# BSB-LAN-Full-SS.net
KiCad netlist of a schematic drawn in EAGLE
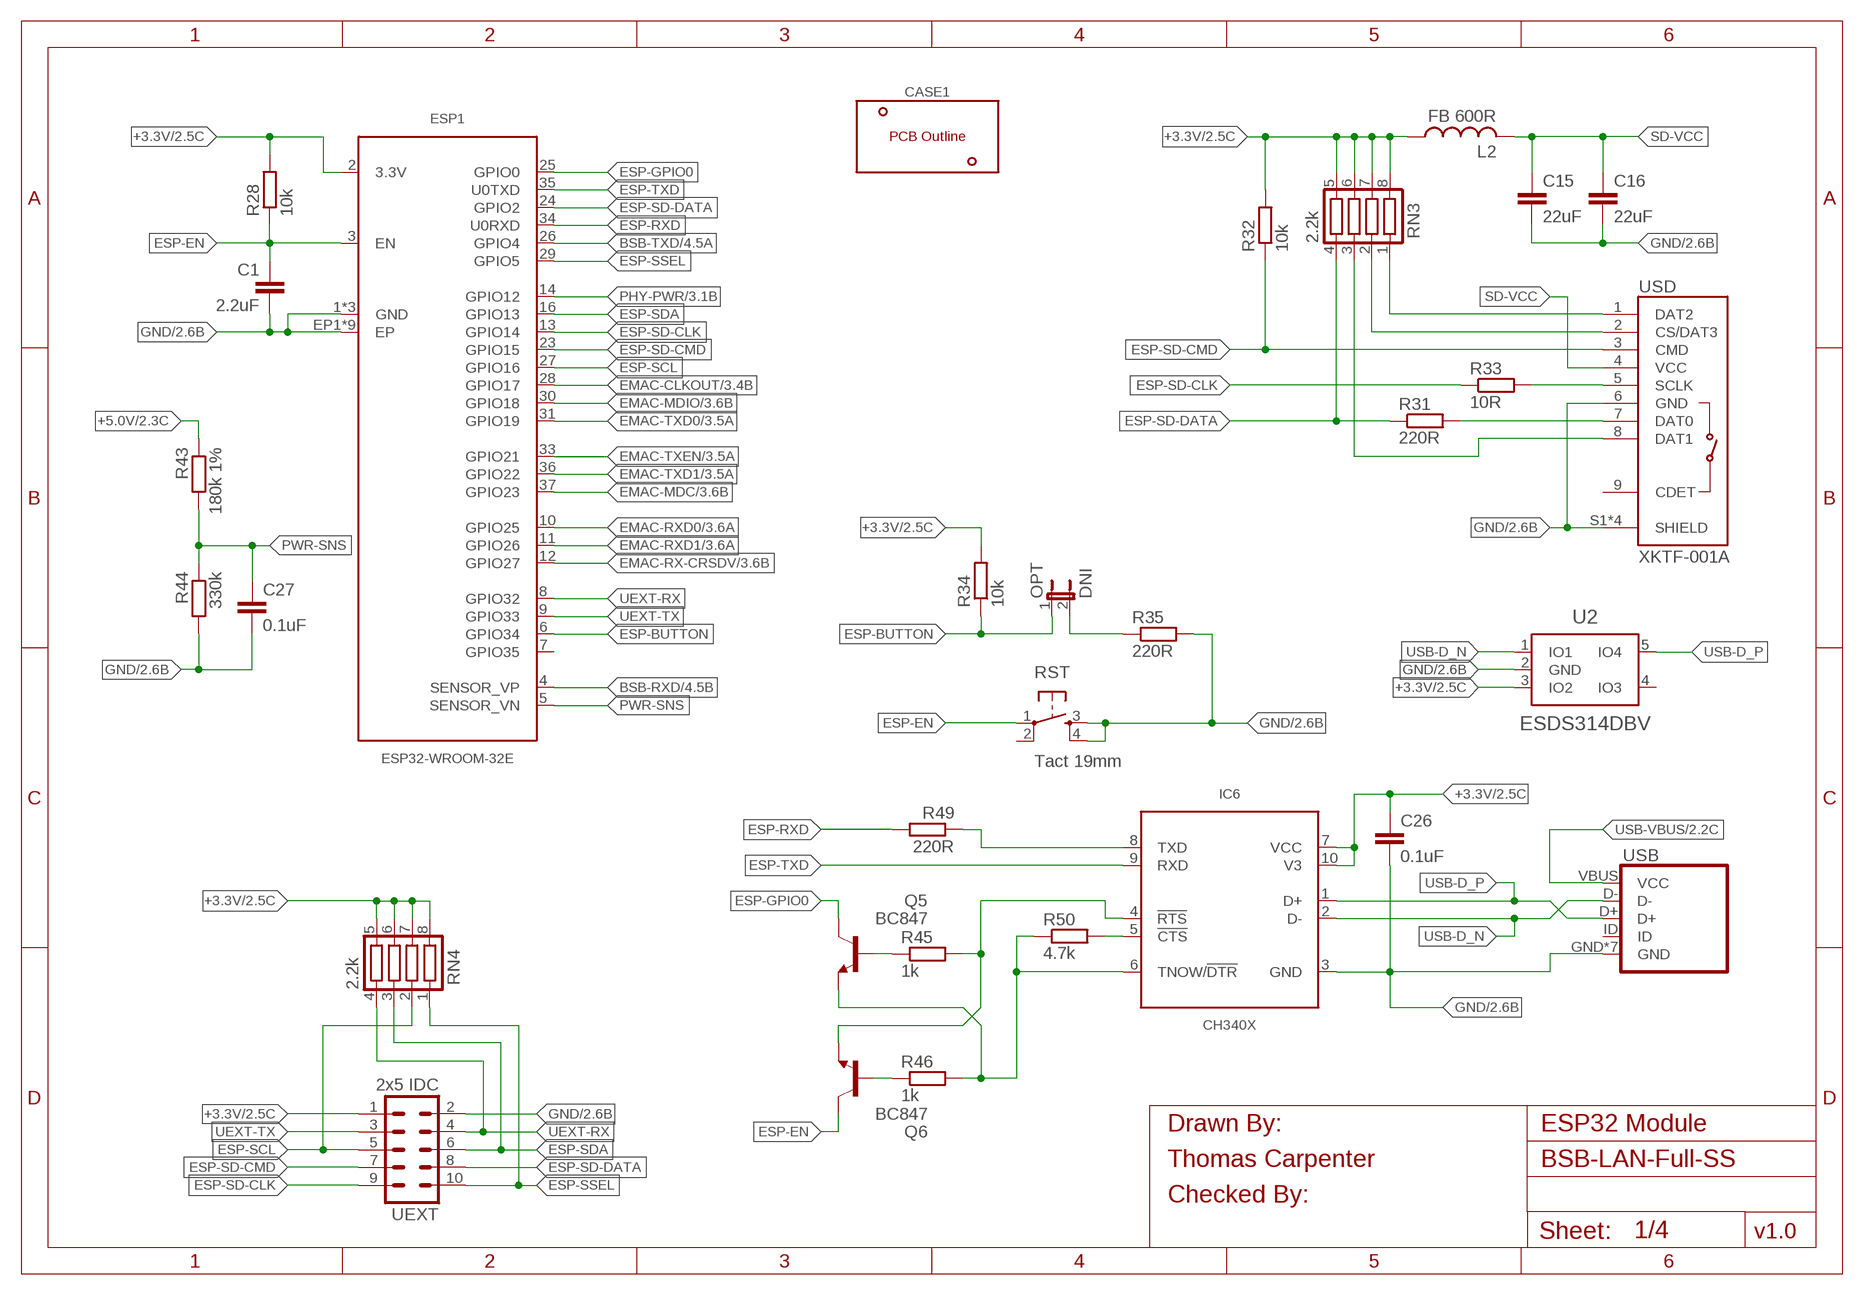
[diagram p0: schematic, sheet 1]
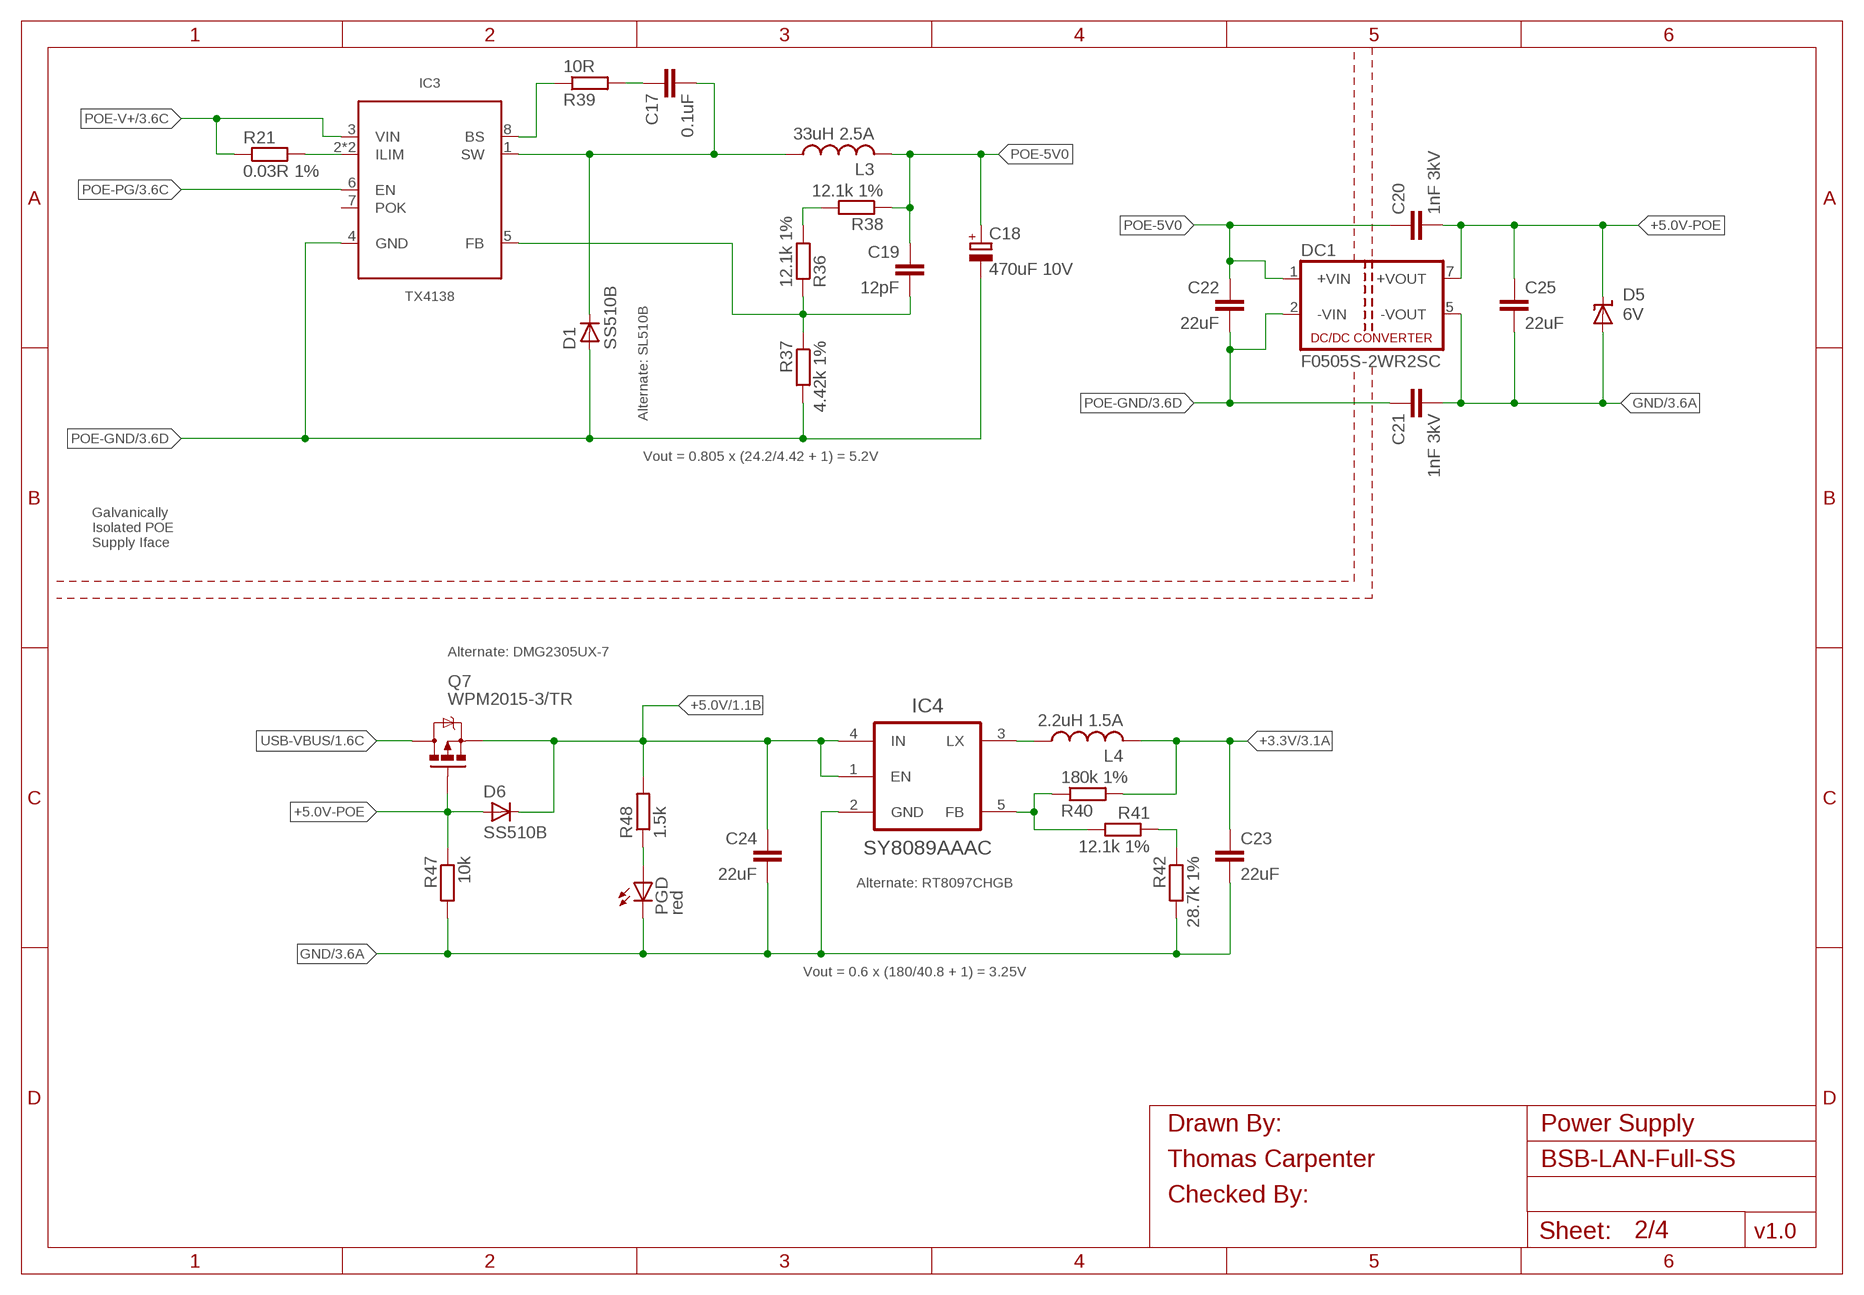
[diagram p1: schematic, sheet 2]
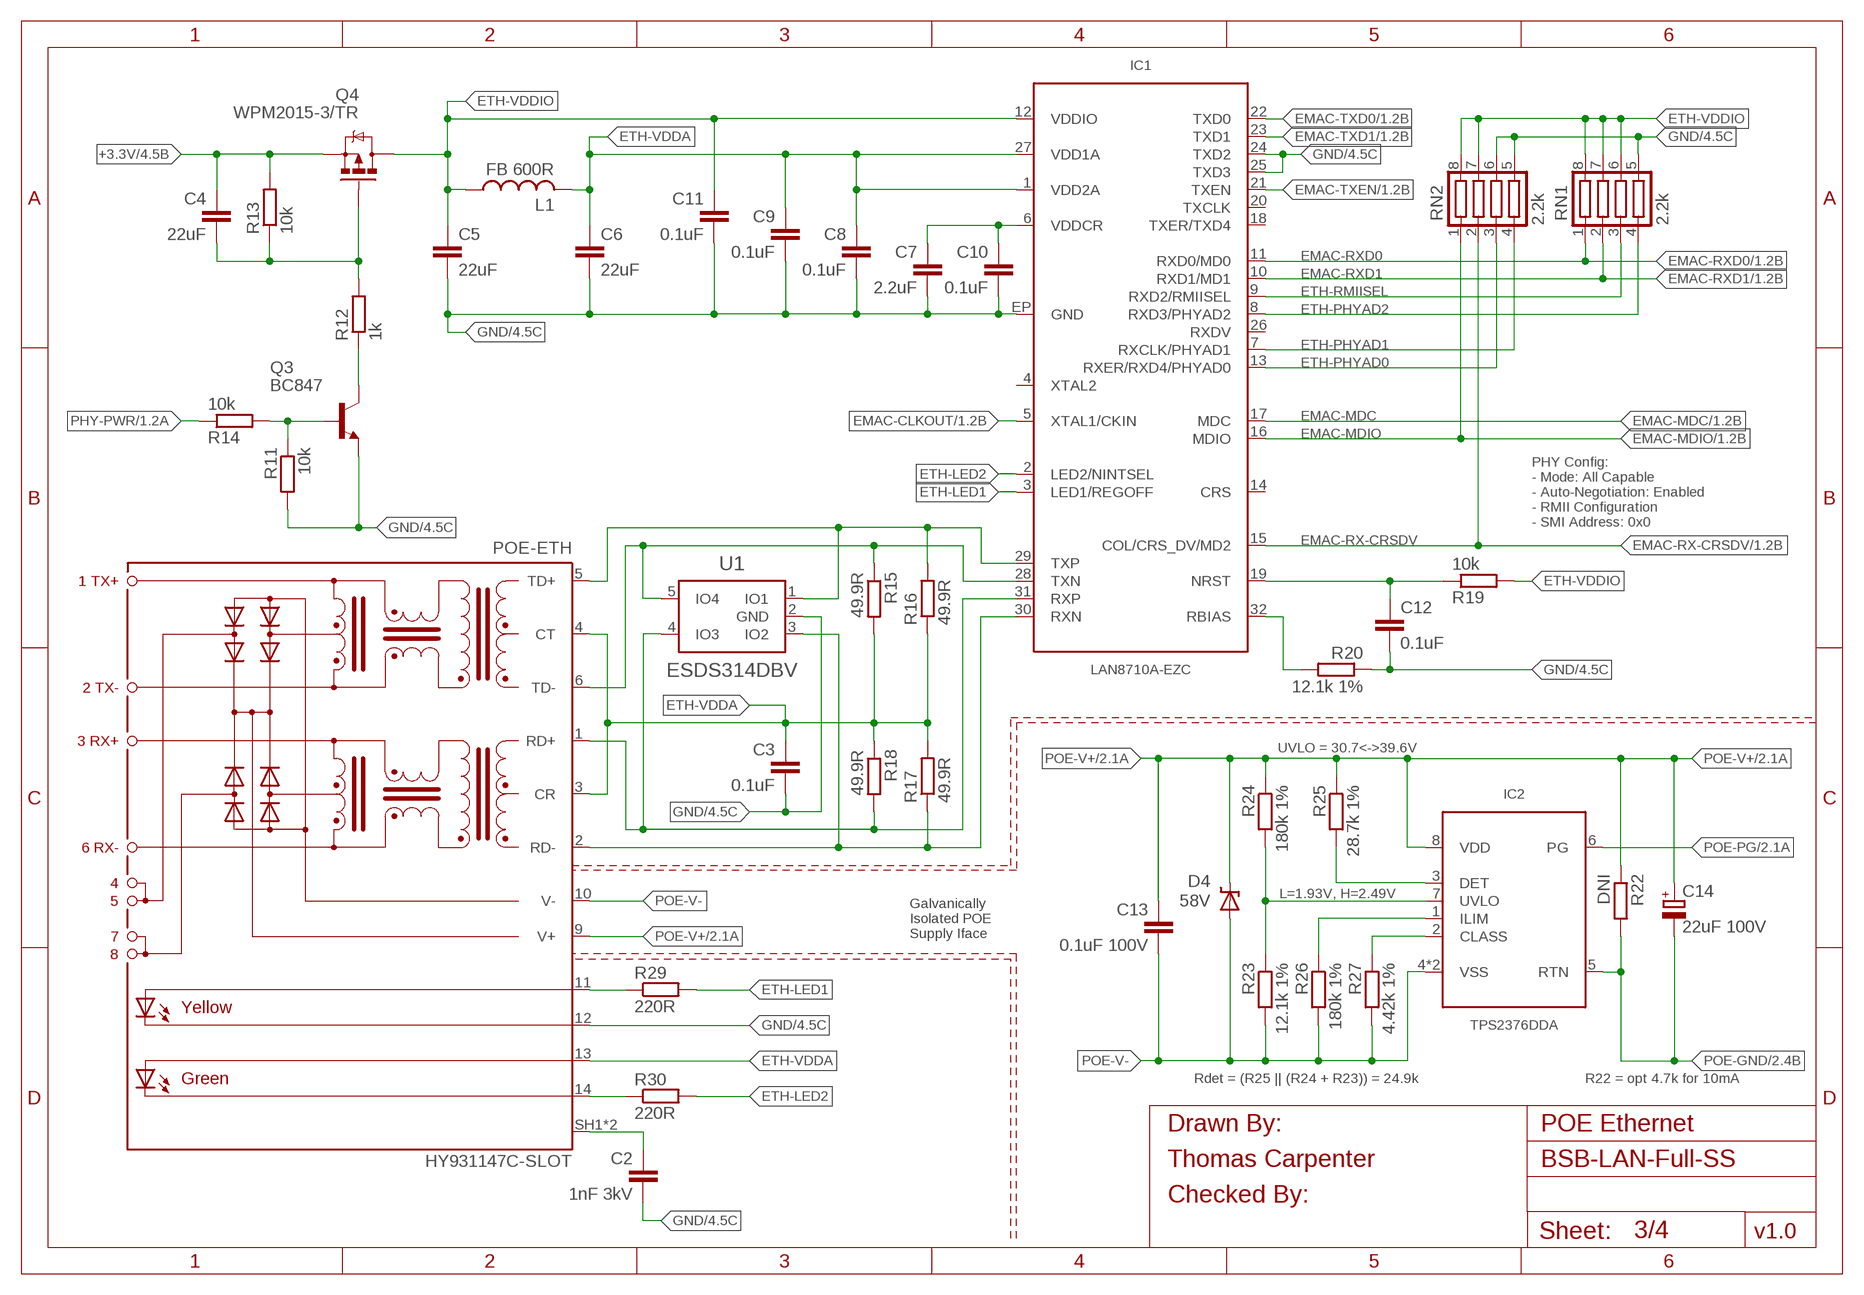
[diagram p2: schematic, sheet 3]
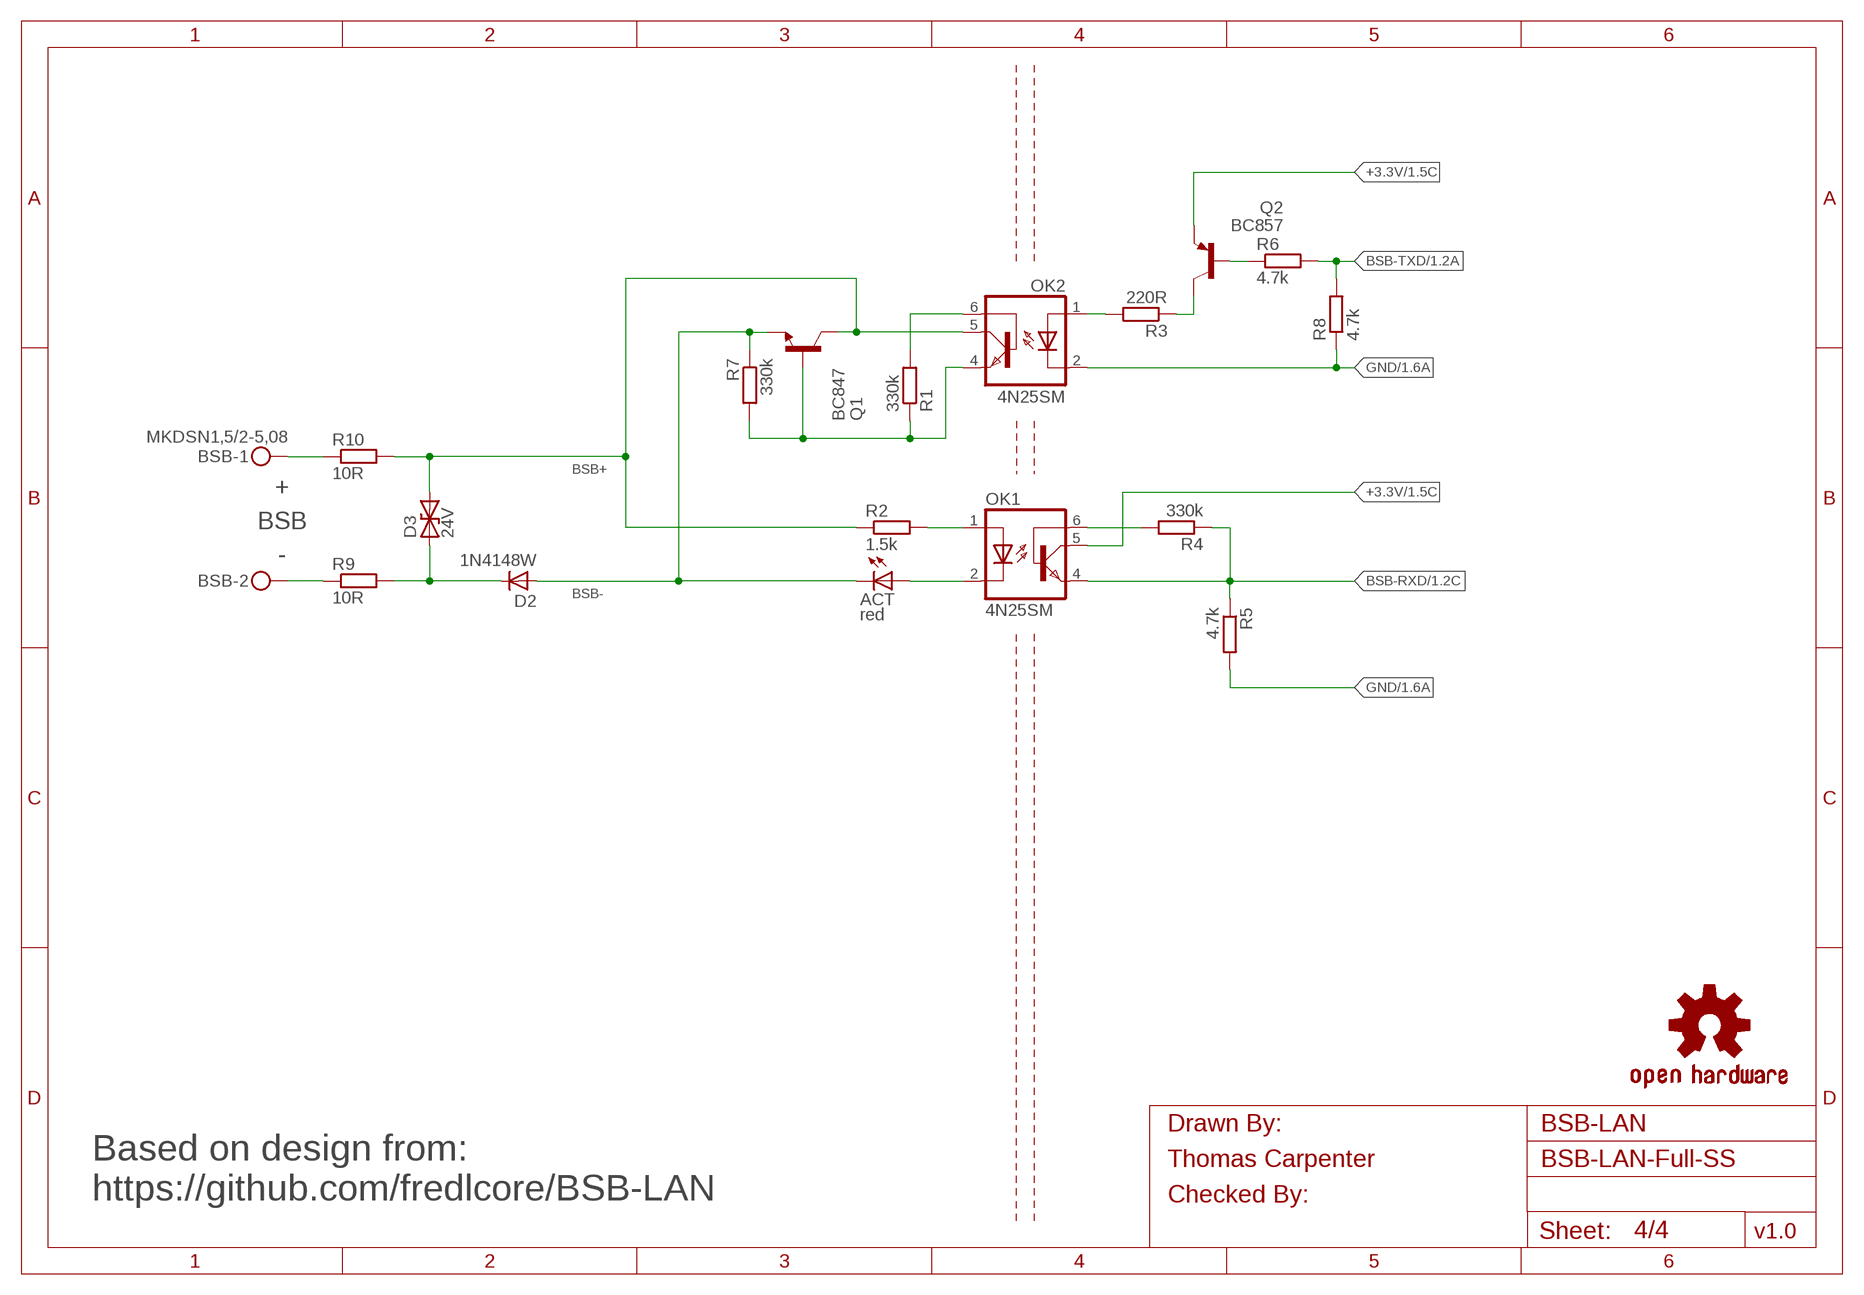
[diagram p3: schematic, sheet 4]

(export (version "E")
  (design (tool "Eeschema 10.0.6"))
  (components
    (comp (ref "C17")
      (value "0.1uF")
      (footprint "eagle-import:C0603L")
      (fields (field (name "LCSC_PART") "C113803"))
      (libsource (lib "eagle-import") (part "C-EUC0603L"))
    )
    (comp (ref "C18")
      (value "470uF 10V")
      (footprint "eagle-import:SMC_D")
      (fields (field (name "LCSC_PART") "C4944894"))
      (libsource (lib "eagle-import") (part "CPOL-EUSMCD"))
    )
    (comp (ref "C19")
      (value "12pF")
      (footprint "eagle-import:C0402")
      (fields (field (name "LCSC_PART") "C1547"))
      (libsource (lib "eagle-import") (part "C-EUC0402"))
    )
    (comp (ref "C20")
      (value "1nF 3kV")
      (footprint "eagle-import:C1808")
      (fields (field (name "LCSC_PART") "C577300"))
      (libsource (lib "eagle-import") (part "C-EUC1808"))
    )
    (comp (ref "C21")
      (value "1nF 3kV")
      (footprint "eagle-import:C1808")
      (fields (field (name "LCSC_PART") "C577300"))
      (libsource (lib "eagle-import") (part "C-EUC1808"))
    )
    (comp (ref "C22")
      (value "22uF")
      (footprint "eagle-import:C0805")
      (fields (field (name "LCSC_PART") "C45783"))
      (libsource (lib "eagle-import") (part "C-EUC0805"))
    )
    (comp (ref "C23")
      (value "22uF")
      (footprint "eagle-import:C0805")
      (fields (field (name "LCSC_PART") "C45783"))
      (libsource (lib "eagle-import") (part "C-EUC0805"))
    )
    (comp (ref "C24")
      (value "22uF")
      (footprint "eagle-import:C0805")
      (fields (field (name "LCSC_PART") "C45783"))
      (libsource (lib "eagle-import") (part "C-EUC0805"))
    )
    (comp (ref "C25")
      (value "22uF")
      (footprint "eagle-import:C0805")
      (fields (field (name "LCSC_PART") "C45783"))
      (libsource (lib "eagle-import") (part "C-EUC0805"))
    )
    (comp (ref "D1")
      (value "SS510B")
      (footprint "eagle-import:SMB")
      (fields (field (name "LCSC_PART") "C65011"))
      (libsource (lib "eagle-import") (part "DIODE-SMB"))
    )
    (comp (ref "D5")
      (value "6V")
      (footprint "eagle-import:SMA")
      (fields (field (name "LCSC_PART") "C223993"))
      (libsource (lib "eagle-import") (part "TVS-UNISMA"))
    )
    (comp (ref "D6")
      (value "SS510B")
      (footprint "eagle-import:SMB")
      (fields (field (name "LCSC_PART") "C65011"))
      (libsource (lib "eagle-import") (part "DIODE-SMB"))
    )
    (comp (ref "DC1")
      (value "F0505S-2WR2SC")
      (footprint "eagle-import:SIP7-N")
      (fields (field (name "LCSC_PART") "C909777"))
      (libsource (lib "eagle-import") (part "FS-2WR2SC0505"))
    )
    (comp (ref "IC3")
      (value "TX4138")
      (footprint "eagle-import:SOIC8-EP")
      (fields (field (name "LCSC_PART") "C329267"))
      (libsource (lib "eagle-import") (part "TX4138"))
    )
    (comp (ref "IC4")
      (value "SY8089AAAC")
      (footprint "eagle-import:DBV0005A-SOT23")
      (fields (field (name "LCSC_PART") "C78988"))
      (libsource (lib "eagle-import") (part "SY8089?CAAA"))
    )
    (comp (ref "L3")
      (value "33uH 2.5A")
      (footprint "eagle-import:L6560P")
      (fields (field (name "LCSC_PART") "C2839927"))
      (libsource (lib "eagle-import") (part "L-USL6560P"))
    )
    (comp (ref "L4")
      (value "2.2uH 1.5A")
      (footprint "eagle-import:L4040P")
      (fields (field (name "LCSC_PART") "C135262"))
      (libsource (lib "eagle-import") (part "L-USL4040P"))
    )
    (comp (ref "PGD")
      (value "red")
      (footprint "eagle-import:CHIP-LED0603")
      (fields (field (name "LCSC_PART") "C2286"))
      (libsource (lib "eagle-import") (part "LEDCHIPLED_0603"))
    )
    (comp (ref "Q7")
      (value "WPM2015-3/TR")
      (footprint "eagle-import:SOT23")
      (fields (field (name "LCSC_PART") "C7472861"))
      (libsource (lib "eagle-import") (part "WPM2015-3/TR"))
    )
    (comp (ref "R21")
      (value "0.03R 1%")
      (footprint "eagle-import:R1206")
      (fields (field (name "LCSC_PART") "C163046"))
      (libsource (lib "eagle-import") (part "R-EU_R1206"))
    )
    (comp (ref "R36")
      (value "12.1k 1%")
      (footprint "eagle-import:R0402")
      (fields (field (name "LCSC_PART") "C25852"))
      (libsource (lib "eagle-import") (part "R-EU_R0402"))
    )
    (comp (ref "R37")
      (value "4.42k 1%")
      (footprint "eagle-import:R0402")
      (fields (field (name "LCSC_PART") "C52269"))
      (libsource (lib "eagle-import") (part "R-EU_R0402"))
    )
    (comp (ref "R38")
      (value "12.1k 1%")
      (footprint "eagle-import:R0402")
      (fields (field (name "LCSC_PART") "C25852"))
      (libsource (lib "eagle-import") (part "R-EU_R0402"))
    )
    (comp (ref "R39")
      (value "10R")
      (footprint "eagle-import:R0603L")
      (fields (field (name "LCSC_PART") "C22859"))
      (libsource (lib "eagle-import") (part "R-EU_R0603L"))
    )
    (comp (ref "R40")
      (value "180k 1%")
      (footprint "eagle-import:R0402")
      (fields (field (name "LCSC_PART") "C25760"))
      (libsource (lib "eagle-import") (part "R-EU_R0402"))
    )
    (comp (ref "R41")
      (value "12.1k 1%")
      (footprint "eagle-import:R0402")
      (fields (field (name "LCSC_PART") "C25852"))
      (libsource (lib "eagle-import") (part "R-EU_R0402"))
    )
    (comp (ref "R42")
      (value "28.7k 1%")
      (footprint "eagle-import:R0402")
      (fields (field (name "LCSC_PART") "C26972"))
      (libsource (lib "eagle-import") (part "R-EU_R0402"))
    )
    (comp (ref "R47")
      (value "10k")
      (footprint "eagle-import:R0402")
      (fields (field (name "LCSC_PART") "C25744"))
      (libsource (lib "eagle-import") (part "R-EU_R0402"))
    )
    (comp (ref "R48")
      (value "1.5k")
      (footprint "eagle-import:R0603")
      (fields (field (name "LCSC_PART") "C22843"))
      (libsource (lib "eagle-import") (part "R-EU_R0603"))
    )
    (comp (ref "C2")
      (value "1nF 3kV")
      (footprint "eagle-import:C1808")
      (fields (field (name "LCSC_PART") "C577300"))
      (libsource (lib "eagle-import") (part "C-EUC1808"))
    )
    (comp (ref "C3")
      (value "0.1uF")
      (footprint "eagle-import:C0402")
      (fields (field (name "LCSC_PART") "C1525"))
      (libsource (lib "eagle-import") (part "C-EUC0402"))
    )
    (comp (ref "C4")
      (value "22uF")
      (footprint "eagle-import:C0805L")
      (fields (field (name "LCSC_PART") "C45783"))
      (libsource (lib "eagle-import") (part "C-EUC0805L"))
    )
    (comp (ref "C5")
      (value "22uF")
      (footprint "eagle-import:C0805L")
      (fields (field (name "LCSC_PART") "C45783"))
      (libsource (lib "eagle-import") (part "C-EUC0805L"))
    )
    (comp (ref "C6")
      (value "22uF")
      (footprint "eagle-import:C0805L")
      (fields (field (name "LCSC_PART") "C45783"))
      (libsource (lib "eagle-import") (part "C-EUC0805L"))
    )
    (comp (ref "C7")
      (value "2.2uF")
      (footprint "eagle-import:C0603")
      (fields (field (name "LCSC_PART") "C23630"))
      (libsource (lib "eagle-import") (part "C-EUC0603"))
    )
    (comp (ref "C8")
      (value "0.1uF")
      (footprint "eagle-import:C0402")
      (fields (field (name "LCSC_PART") "C1525"))
      (libsource (lib "eagle-import") (part "C-EUC0402"))
    )
    (comp (ref "C9")
      (value "0.1uF")
      (footprint "eagle-import:C0402")
      (fields (field (name "LCSC_PART") "C1525"))
      (libsource (lib "eagle-import") (part "C-EUC0402"))
    )
    (comp (ref "C10")
      (value "0.1uF")
      (footprint "eagle-import:C0402")
      (fields (field (name "LCSC_PART") "C1525"))
      (libsource (lib "eagle-import") (part "C-EUC0402"))
    )
    (comp (ref "C11")
      (value "0.1uF")
      (footprint "eagle-import:C0402")
      (fields (field (name "LCSC_PART") "C1525"))
      (libsource (lib "eagle-import") (part "C-EUC0402"))
    )
    (comp (ref "C12")
      (value "0.1uF")
      (footprint "eagle-import:C0402")
      (fields (field (name "LCSC_PART") "C1525"))
      (libsource (lib "eagle-import") (part "C-EUC0402"))
    )
    (comp (ref "C13")
      (value "0.1uF 100V")
      (footprint "eagle-import:C0603")
      (fields (field (name "LCSC_PART") "C113803"))
      (libsource (lib "eagle-import") (part "C-EUC0603"))
    )
    (comp (ref "C14")
      (value "22uF 100V")
      (footprint "eagle-import:PANASONIC_D")
      (fields (field (name "LCSC_PART") "C487431"))
      (libsource (lib "eagle-import") (part "CPOL-EUD"))
    )
    (comp (ref "D4")
      (value "58V")
      (footprint "eagle-import:SMA")
      (fields (field (name "LCSC_PART") "C151246"))
      (libsource (lib "eagle-import") (part "TVS-UNISMA"))
    )
    (comp (ref "IC1")
      (value "LAN8710A-EZC")
      (footprint "eagle-import:QFN-5X5-32")
      (fields (field (name "LCSC_PART") "C46185"))
      (libsource (lib "eagle-import") (part "LAN8710A-EZC"))
    )
    (comp (ref "IC2")
      (value "TPS2376DDA")
      (footprint "eagle-import:SOIC8-EP")
      (fields (field (name "LCSC_PART") "C544899"))
      (libsource (lib "eagle-import") (part "TPS237DDA6"))
    )
    (comp (ref "L1")
      (value "FB 600R")
      (footprint "eagle-import:L2010")
      (fields (field (name "LCSC_PART") "C1017"))
      (libsource (lib "eagle-import") (part "L-USL0805"))
    )
    (comp (ref "POE-ETH")
      (value "HY931147C-SLOT")
      (footprint "eagle-import:HY931147C-SLOT")
      (fields (field (name "LCSC_PART") "C91754"))
      (libsource (lib "eagle-import") (part "HY931147C-SLOT"))
    )
    (comp (ref "Q3")
      (value "BC847")
      (footprint "eagle-import:SOT23")
      (fields (field (name "LCSC_PART") "C130417"))
      (libsource (lib "eagle-import") (part "BC847"))
    )
    (comp (ref "Q4")
      (value "WPM2015-3/TR")
      (footprint "eagle-import:SOT23")
      (fields (field (name "LCSC_PART") "C7472861"))
      (libsource (lib "eagle-import") (part "WPM2015-3/TR"))
    )
    (comp (ref "R11")
      (value "10k")
      (footprint "eagle-import:R0402")
      (fields (field (name "LCSC_PART") "C25744"))
      (libsource (lib "eagle-import") (part "R-EU_R0402"))
    )
    (comp (ref "R12")
      (value "1k")
      (footprint "eagle-import:R0402")
      (fields (field (name "LCSC_PART") "C11702"))
      (libsource (lib "eagle-import") (part "R-EU_R0402"))
    )
    (comp (ref "R13")
      (value "10k")
      (footprint "eagle-import:R0402")
      (fields (field (name "LCSC_PART") "C25744"))
      (libsource (lib "eagle-import") (part "R-EU_R0402"))
    )
    (comp (ref "R14")
      (value "10k")
      (footprint "eagle-import:R0402")
      (fields (field (name "LCSC_PART") "C25744"))
      (libsource (lib "eagle-import") (part "R-EU_R0402"))
    )
    (comp (ref "R15")
      (value "49.9R")
      (footprint "eagle-import:R0402L")
      (fields (field (name "LCSC_PART") "C25120"))
      (libsource (lib "eagle-import") (part "R-EU_R0402L"))
    )
    (comp (ref "R16")
      (value "49.9R")
      (footprint "eagle-import:R0402L")
      (fields (field (name "LCSC_PART") "C25120"))
      (libsource (lib "eagle-import") (part "R-EU_R0402L"))
    )
    (comp (ref "R17")
      (value "49.9R")
      (footprint "eagle-import:R0402L")
      (fields (field (name "LCSC_PART") "C25120"))
      (libsource (lib "eagle-import") (part "R-EU_R0402L"))
    )
    (comp (ref "R18")
      (value "49.9R")
      (footprint "eagle-import:R0402L")
      (fields (field (name "LCSC_PART") "C25120"))
      (libsource (lib "eagle-import") (part "R-EU_R0402L"))
    )
    (comp (ref "R19")
      (value "10k")
      (footprint "eagle-import:R0402")
      (fields (field (name "LCSC_PART") "C25744"))
      (libsource (lib "eagle-import") (part "R-EU_R0402"))
    )
    (comp (ref "R20")
      (value "12.1k 1%")
      (footprint "eagle-import:R0402")
      (fields (field (name "LCSC_PART") "C25852"))
      (libsource (lib "eagle-import") (part "R-EU_R0402"))
    )
    (comp (ref "R22")
      (value "DNI")
      (footprint "eagle-import:R1206")
      (libsource (lib "eagle-import") (part "R-EU_R1206"))
    )
    (comp (ref "R23")
      (value "12.1k 1%")
      (footprint "eagle-import:R0402")
      (fields (field (name "LCSC_PART") "C25852"))
      (libsource (lib "eagle-import") (part "R-EU_R0402"))
    )
    (comp (ref "R24")
      (value "180k 1%")
      (footprint "eagle-import:R0402")
      (fields (field (name "LCSC_PART") "C25760"))
      (libsource (lib "eagle-import") (part "R-EU_R0402"))
    )
    (comp (ref "R25")
      (value "28.7k 1%")
      (footprint "eagle-import:R0402")
      (fields (field (name "LCSC_PART") "C26972"))
      (libsource (lib "eagle-import") (part "R-EU_R0402"))
    )
    (comp (ref "R26")
      (value "180k 1%")
      (footprint "eagle-import:R0402")
      (fields (field (name "LCSC_PART") "C25760"))
      (libsource (lib "eagle-import") (part "R-EU_R0402"))
    )
    (comp (ref "R27")
      (value "4.42k 1%")
      (footprint "eagle-import:R0402")
      (fields (field (name "LCSC_PART") "C52269"))
      (libsource (lib "eagle-import") (part "R-EU_R0402"))
    )
    (comp (ref "R29")
      (value "220R")
      (footprint "eagle-import:R0402")
      (fields (field (name "LCSC_PART") "C25091"))
      (libsource (lib "eagle-import") (part "R-EU_R0402"))
    )
    (comp (ref "R30")
      (value "220R")
      (footprint "eagle-import:R0402")
      (fields (field (name "LCSC_PART") "C25091"))
      (libsource (lib "eagle-import") (part "R-EU_R0402"))
    )
    (comp (ref "RN1")
      (value "2.2k")
      (footprint "eagle-import:CTS742C083")
      (fields (field (name "LCSC_PART") "C414564"))
      (libsource (lib "eagle-import") (part "R-NET-04-R1206"))
    )
    (comp (ref "RN2")
      (value "2.2k")
      (footprint "eagle-import:CTS742C083")
      (fields (field (name "LCSC_PART") "C414564"))
      (libsource (lib "eagle-import") (part "R-NET-04-R1206"))
    )
    (comp (ref "U1")
      (value "ESDS314DBV")
      (footprint "eagle-import:DBV0005A-SOT23")
      (fields (field (name "LCSC_PART") "C1847859"))
      (libsource (lib "eagle-import") (part "ESDS314DBV"))
    )
    (comp (ref "ACT")
      (value "red")
      (footprint "eagle-import:CHIP-LED0603")
      (fields (field (name "LCSC_PART") "C2286"))
      (libsource (lib "eagle-import") (part "LEDCHIPLED_0603"))
    )
    (comp (ref "BSB")
      (value "MKDSN1,5/2-5,08")
      (footprint "eagle-import:MKDSN1_5-2-5_08")
      (fields (field (name "LCSC_PART") "C5183989"))
      (libsource (lib "eagle-import") (part "MKDSN1,5/2-5,08"))
    )
    (comp (ref "D2")
      (value "1N4148W")
      (footprint "eagle-import:SOD123")
      (fields (field (name "LCSC_PART") "C81598"))
      (libsource (lib "eagle-import") (part "DIODE-SOD123"))
    )
    (comp (ref "D3")
      (value "24V")
      (footprint "eagle-import:SMBG")
      (fields (field (name "LCSC_PART") "C83268"))
      (libsource (lib "eagle-import") (part "TVS-BIDIRSMB"))
    )
    (comp (ref "OK1")
      (value "4N25SM")
      (footprint "eagle-import:DIL6-SMD")
      (fields (field (name "LCSC_PART") "C258246") (field (name "LCSC_PART_1") "C258246"))
      (libsource (lib "eagle-import") (part "4N?MS25"))
    )
    (comp (ref "OK2")
      (value "4N25SM")
      (footprint "eagle-import:DIL6-SMD")
      (fields (field (name "LCSC_PART") "C258246") (field (name "LCSC_PART_1") "C258246"))
      (libsource (lib "eagle-import") (part "4N?MS25"))
    )
    (comp (ref "Q1")
      (value "BC847")
      (footprint "eagle-import:SOT23")
      (fields (field (name "LCSC_PART") "C130417") (field (name "LCSC_PART_1") "C130417"))
      (libsource (lib "eagle-import") (part "BC847"))
    )
    (comp (ref "Q2")
      (value "BC857")
      (footprint "eagle-import:SOT23-BEC")
      (fields (field (name "LCSC_PART") "C426782") (field (name "LCSC_PART_1") "C426782"))
      (libsource (lib "eagle-import") (part "BC857"))
    )
    (comp (ref "R1")
      (value "330k")
      (footprint "eagle-import:R0603")
      (fields (field (name "LCSC_PART") "C23137"))
      (libsource (lib "eagle-import") (part "R-EU_R0603"))
    )
    (comp (ref "R2")
      (value "1.5k")
      (footprint "eagle-import:R0603")
      (fields (field (name "LCSC_PART") "C22843"))
      (libsource (lib "eagle-import") (part "R-EU_R0603"))
    )
    (comp (ref "R3")
      (value "220R")
      (footprint "eagle-import:R0402")
      (fields (field (name "LCSC_PART") "C25091"))
      (libsource (lib "eagle-import") (part "R-EU_R0402"))
    )
    (comp (ref "R4")
      (value "330k")
      (footprint "eagle-import:R0603")
      (fields (field (name "LCSC_PART") "C23137"))
      (libsource (lib "eagle-import") (part "R-EU_R0603"))
    )
    (comp (ref "R5")
      (value "4.7k")
      (footprint "eagle-import:R0402")
      (fields (field (name "LCSC_PART") "C25900"))
      (libsource (lib "eagle-import") (part "R-EU_R0402"))
    )
    (comp (ref "R6")
      (value "4.7k")
      (footprint "eagle-import:R0402")
      (fields (field (name "LCSC_PART") "C25900"))
      (libsource (lib "eagle-import") (part "R-EU_R0402"))
    )
    (comp (ref "R7")
      (value "330k")
      (footprint "eagle-import:R0603")
      (fields (field (name "LCSC_PART") "C23137"))
      (libsource (lib "eagle-import") (part "R-EU_R0603"))
    )
    (comp (ref "R8")
      (value "4.7k")
      (footprint "eagle-import:R0402")
      (fields (field (name "LCSC_PART") "C25900"))
      (libsource (lib "eagle-import") (part "R-EU_R0402"))
    )
    (comp (ref "R9")
      (value "10R")
      (footprint "eagle-import:R0603")
      (fields (field (name "LCSC_PART") "C22859"))
      (libsource (lib "eagle-import") (part "R-EU_R0603"))
    )
    (comp (ref "R10")
      (value "10R")
      (footprint "eagle-import:R0603")
      (fields (field (name "LCSC_PART") "C22859"))
      (libsource (lib "eagle-import") (part "R-EU_R0603"))
    )
    (comp (ref "U$3")
      (value "DNI")
      (footprint "eagle-import:OSHW-LOGO-M")
      (libsource (lib "eagle-import") (part "OSHW-LOGOM"))
    )
    (comp (ref "C1")
      (value "2.2uF")
      (footprint "eagle-import:C0603")
      (fields (field (name "LCSC_PART") "C23630"))
      (libsource (lib "eagle-import") (part "C-EUC0603"))
    )
    (comp (ref "C15")
      (value "22uF")
      (footprint "eagle-import:C0805L")
      (fields (field (name "LCSC_PART") "C45783"))
      (libsource (lib "eagle-import") (part "C-EUC0805L"))
    )
    (comp (ref "C16")
      (value "22uF")
      (footprint "eagle-import:C0805L")
      (fields (field (name "LCSC_PART") "C45783"))
      (libsource (lib "eagle-import") (part "C-EUC0805L"))
    )
    (comp (ref "C26")
      (value "0.1uF")
      (footprint "eagle-import:C0402")
      (fields (field (name "LCSC_PART") "C1525"))
      (libsource (lib "eagle-import") (part "C-EUC0402"))
    )
    (comp (ref "C27")
      (value "0.1uF")
      (footprint "eagle-import:C0402")
      (fields (field (name "LCSC_PART") "C1525"))
      (libsource (lib "eagle-import") (part "C-EUC0402"))
    )
    (comp (ref "CASE1")
      (value "DNI")
      (footprint "eagle-import:CNMB_3-")
      (libsource (lib "eagle-import") (part "CNMB/3"))
    )
    (comp (ref "ESP1")
      (value "ESP32-WROOM-32E")
      (footprint "eagle-import:ESP32-WROOM-32E")
      (fields (field (name "LCSC_PART") "C701341"))
      (libsource (lib "eagle-import") (part "ESP32-WROOM-32E"))
    )
    (comp (ref "IC6")
      (value "CH340X")
      (footprint "eagle-import:MSOP10")
      (fields (field (name "LCSC_PART") "C3035748"))
      (libsource (lib "eagle-import") (part "CH340X"))
    )
    (comp (ref "L2")
      (value "FB 600R")
      (footprint "eagle-import:L2010")
      (fields (field (name "LCSC_PART") "C1017"))
      (libsource (lib "eagle-import") (part "L-USL0805"))
    )
    (comp (ref "OPT")
      (value "DNI")
      (footprint "eagle-import:1X02")
      (libsource (lib "eagle-import") (part "JUMPER-2-PTH"))
    )
    (comp (ref "Q5")
      (value "BC847")
      (footprint "eagle-import:SOT23")
      (fields (field (name "LCSC_PART") "C130417") (field (name "LCSC_PART_1") "C130417"))
      (libsource (lib "eagle-import") (part "BC847"))
    )
    (comp (ref "Q6")
      (value "BC847")
      (footprint "eagle-import:SOT23")
      (fields (field (name "LCSC_PART") "C130417"))
      (libsource (lib "eagle-import") (part "BC847"))
    )
    (comp (ref "R28")
      (value "10k")
      (footprint "eagle-import:R0402")
      (fields (field (name "LCSC_PART") "C25744"))
      (libsource (lib "eagle-import") (part "R-EU_R0402"))
    )
    (comp (ref "R31")
      (value "220R")
      (footprint "eagle-import:R0402")
      (fields (field (name "LCSC_PART") "C25091"))
      (libsource (lib "eagle-import") (part "R-EU_R0402"))
    )
    (comp (ref "R32")
      (value "10k")
      (footprint "eagle-import:R0402")
      (fields (field (name "LCSC_PART") "C25744"))
      (libsource (lib "eagle-import") (part "R-EU_R0402"))
    )
    (comp (ref "R33")
      (value "10R")
      (footprint "eagle-import:R0603L")
      (fields (field (name "LCSC_PART") "C22859"))
      (libsource (lib "eagle-import") (part "R-EU_R0603L"))
    )
    (comp (ref "R34")
      (value "10k")
      (footprint "eagle-import:R0402")
      (fields (field (name "LCSC_PART") "C25744"))
      (libsource (lib "eagle-import") (part "R-EU_R0402"))
    )
    (comp (ref "R35")
      (value "220R")
      (footprint "eagle-import:R0402")
      (fields (field (name "LCSC_PART") "C25091"))
      (libsource (lib "eagle-import") (part "R-EU_R0402"))
    )
    (comp (ref "R43")
      (value "180k 1%")
      (footprint "eagle-import:R0402")
      (fields (field (name "LCSC_PART") "C25760"))
      (libsource (lib "eagle-import") (part "R-EU_R0402"))
    )
    (comp (ref "R44")
      (value "330k")
      (footprint "eagle-import:R0603L")
      (fields (field (name "LCSC_PART") "C23137"))
      (libsource (lib "eagle-import") (part "R-EU_R0603L"))
    )
    (comp (ref "R45")
      (value "1k")
      (footprint "eagle-import:R0402")
      (fields (field (name "LCSC_PART") "C11702"))
      (libsource (lib "eagle-import") (part "R-EU_R0402"))
    )
    (comp (ref "R46")
      (value "1k")
      (footprint "eagle-import:R0402")
      (fields (field (name "LCSC_PART") "C11702"))
      (libsource (lib "eagle-import") (part "R-EU_R0402"))
    )
    (comp (ref "R49")
      (value "220R")
      (footprint "eagle-import:R0402")
      (fields (field (name "LCSC_PART") "C25091"))
      (libsource (lib "eagle-import") (part "R-EU_R0402"))
    )
    (comp (ref "R50")
      (value "4.7k")
      (footprint "eagle-import:R0402")
      (fields (field (name "LCSC_PART") "C25900"))
      (libsource (lib "eagle-import") (part "R-EU_R0402"))
    )
    (comp (ref "RN3")
      (value "2.2k")
      (footprint "eagle-import:CTS742C083")
      (fields (field (name "LCSC_PART") "C414564"))
      (libsource (lib "eagle-import") (part "R-NET-04-R1206"))
    )
    (comp (ref "RN4")
      (value "2.2k")
      (footprint "eagle-import:CTS742C083")
      (fields (field (name "LCSC_PART") "C414564"))
      (libsource (lib "eagle-import") (part "R-NET-04-R1206"))
    )
    (comp (ref "RST")
      (value "Tact 19mm")
      (footprint "eagle-import:TACTILE_SWITCH")
      (fields (field (name "LCSC_PART") "C13828") (field (name "LCSC_PART_1") "C2837529"))
      (libsource (lib "eagle-import") (part "SWITCH-MOMENTARY"))
    )
    (comp (ref "U2")
      (value "ESDS314DBV")
      (footprint "eagle-import:DBV0005A-SOT23")
      (fields (field (name "LCSC_PART") "C1847859"))
      (libsource (lib "eagle-import") (part "ESDS314DBV"))
    )
    (comp (ref "UEXT")
      (value "2x5 IDC")
      (footprint "eagle-import:ML10")
      (fields (field (name "LCSC_PART") "C5665"))
      (libsource (lib "eagle-import") (part "ML10"))
    )
    (comp (ref "USB")
      (value "ZX62-B-5PA(33)")
      (footprint "eagle-import:USB-MICROB")
      (fields (field (name "LCSC_PART") "C132561"))
      (libsource (lib "eagle-import") (part "USB_MICROB_PLUG"))
    )
    (comp (ref "USD")
      (value "XKTF-001A")
      (footprint "eagle-import:MICRO-SD")
      (fields (field (name "LCSC_PART") "C381079"))
      (libsource (lib "eagle-import") (part "MICROSD"))
    )
  )
  (nets
    (net (code "1") (name "+3.3V") (class "Default")
      (node (ref "C23") (pin "1") (pinfunction "1_1") (pintype "passive"))
      (node (ref "C26") (pin "1") (pinfunction "1_1") (pintype "passive"))
      (node (ref "C4") (pin "1") (pinfunction "1_1") (pintype "passive"))
      (node (ref "ESP1") (pin "2") (pinfunction "3.3V_2") (pintype "power_in"))
      (node (ref "IC6") (pin "10") (pinfunction "V3_10") (pintype "power_in"))
      (node (ref "IC6") (pin "7") (pinfunction "VCC_7") (pintype "power_in"))
      (node (ref "L2") (pin "1") (pinfunction "1_1") (pintype "passive"))
      (node (ref "L4") (pin "2") (pinfunction "2_2") (pintype "passive"))
      (node (ref "OK1") (pin "5") (pinfunction "COL_5") (pintype "passive"))
      (node (ref "Q2") (pin "E") (pinfunction "E_E") (pintype "passive"))
      (node (ref "Q4") (pin "2") (pinfunction "S_2") (pintype "passive"))
      (node (ref "R13") (pin "2") (pinfunction "2_2") (pintype "passive"))
      (node (ref "R28") (pin "2") (pinfunction "2_2") (pintype "passive"))
      (node (ref "R32") (pin "2") (pinfunction "2_2") (pintype "passive"))
      (node (ref "R34") (pin "2") (pinfunction "2_2") (pintype "passive"))
      (node (ref "R40") (pin "2") (pinfunction "2_2") (pintype "passive"))
      (node (ref "RN3") (pin "5") (pinfunction "5_5") (pintype "passive"))
      (node (ref "RN3") (pin "6") (pinfunction "6_6") (pintype "passive"))
      (node (ref "RN3") (pin "7") (pinfunction "7_7") (pintype "passive"))
      (node (ref "RN3") (pin "8") (pinfunction "8_8") (pintype "passive"))
      (node (ref "RN4") (pin "5") (pinfunction "5_5") (pintype "passive"))
      (node (ref "RN4") (pin "6") (pinfunction "6_6") (pintype "passive"))
      (node (ref "RN4") (pin "7") (pinfunction "7_7") (pintype "passive"))
      (node (ref "RN4") (pin "8") (pinfunction "8_8") (pintype "passive"))
      (node (ref "U2") (pin "3") (pinfunction "IO2_3") (pintype "passive"))
      (node (ref "UEXT") (pin "1") (pinfunction "1_1") (pintype "passive"))
    )
    (net (code "2") (name "+5.0V") (class "Default")
      (node (ref "C24") (pin "1") (pinfunction "1_1") (pintype "passive"))
      (node (ref "D6") (pin "C") (pinfunction "C_C") (pintype "passive"))
      (node (ref "IC4") (pin "1") (pinfunction "EN_1") (pintype "input"))
      (node (ref "IC4") (pin "4") (pinfunction "IN_4") (pintype "power_in"))
      (node (ref "Q7") (pin "2") (pinfunction "S_2") (pintype "passive"))
      (node (ref "R43") (pin "1") (pinfunction "1_1") (pintype "passive"))
      (node (ref "R48") (pin "2") (pinfunction "2_2") (pintype "passive"))
    )
    (net (code "3") (name "+5.0V-POE") (class "Default")
      (node (ref "C20") (pin "2") (pinfunction "2_2") (pintype "passive"))
      (node (ref "C25") (pin "1") (pinfunction "1_1") (pintype "passive"))
      (node (ref "D5") (pin "C") (pinfunction "C_C") (pintype "passive"))
      (node (ref "D6") (pin "A") (pinfunction "A_A") (pintype "passive"))
      (node (ref "DC1") (pin "7") (pinfunction "+VOUT_7") (pintype "passive"))
      (node (ref "Q7") (pin "1") (pinfunction "G_1") (pintype "passive"))
      (node (ref "R47") (pin "1") (pinfunction "1_1") (pintype "passive"))
    )
    (net (code "4") (name "BSB+") (class "Default")
      (node (ref "D3") (pin "2") (pinfunction "2_2") (pintype "passive"))
      (node (ref "OK2") (pin "5") (pinfunction "COL_5") (pintype "passive"))
      (node (ref "Q1") (pin "3") (pinfunction "C_3") (pintype "passive"))
      (node (ref "R10") (pin "2") (pinfunction "2_2") (pintype "passive"))
      (node (ref "R2") (pin "1") (pinfunction "1_1") (pintype "passive"))
    )
    (net (code "5") (name "BSB-") (class "Default")
      (node (ref "ACT") (pin "C") (pinfunction "C_C") (pintype "passive"))
      (node (ref "D2") (pin "A") (pinfunction "A_A") (pintype "passive"))
      (node (ref "Q1") (pin "2") (pinfunction "E_2") (pintype "passive"))
      (node (ref "R7") (pin "1") (pinfunction "1_1") (pintype "passive"))
    )
    (net (code "6") (name "BSB-RXD") (class "Default")
      (node (ref "ESP1") (pin "4") (pinfunction "SENSOR_VP_4") (pintype "bidirectional"))
      (node (ref "OK1") (pin "4") (pinfunction "EMI_4") (pintype "passive"))
      (node (ref "R4") (pin "1") (pinfunction "1_1") (pintype "passive"))
      (node (ref "R5") (pin "1") (pinfunction "1_1") (pintype "passive"))
    )
    (net (code "7") (name "BSB-TXD") (class "Default")
      (node (ref "ESP1") (pin "26") (pinfunction "GPIO4_26") (pintype "bidirectional"))
      (node (ref "R6") (pin "2") (pinfunction "2_2") (pintype "passive"))
      (node (ref "R8") (pin "2") (pinfunction "2_2") (pintype "passive"))
    )
    (net (code "8") (name "EMAC-CLKOUT") (class "Default")
      (node (ref "ESP1") (pin "28") (pinfunction "GPIO17_28") (pintype "bidirectional"))
      (node (ref "IC1") (pin "5") (pinfunction "XTAL1/CKIN_5") (pintype "input"))
    )
    (net (code "9") (name "EMAC-MDC") (class "Default")
      (node (ref "ESP1") (pin "37") (pinfunction "GPIO23_37") (pintype "bidirectional"))
      (node (ref "IC1") (pin "17") (pinfunction "MDC_17") (pintype "input"))
    )
    (net (code "10") (name "EMAC-MDIO") (class "Default")
      (node (ref "ESP1") (pin "30") (pinfunction "GPIO18_30") (pintype "bidirectional"))
      (node (ref "IC1") (pin "16") (pinfunction "MDIO_16") (pintype "bidirectional"))
      (node (ref "RN2") (pin "1") (pinfunction "1_1") (pintype "passive"))
    )
    (net (code "11") (name "EMAC-RX-CRSDV") (class "Default")
      (node (ref "ESP1") (pin "12") (pinfunction "GPIO27_12") (pintype "bidirectional"))
      (node (ref "IC1") (pin "15") (pinfunction "COL/CRS_DV/MD2_15") (pintype "bidirectional"))
      (node (ref "RN2") (pin "2") (pinfunction "2_2") (pintype "passive"))
    )
    (net (code "12") (name "EMAC-RXD0") (class "Default")
      (node (ref "ESP1") (pin "10") (pinfunction "GPIO25_10") (pintype "bidirectional"))
      (node (ref "IC1") (pin "11") (pinfunction "RXD0/MD0_11") (pintype "bidirectional"))
      (node (ref "RN1") (pin "1") (pinfunction "1_1") (pintype "passive"))
    )
    (net (code "13") (name "EMAC-RXD1") (class "Default")
      (node (ref "ESP1") (pin "11") (pinfunction "GPIO26_11") (pintype "bidirectional"))
      (node (ref "IC1") (pin "10") (pinfunction "RXD1/MD1_10") (pintype "bidirectional"))
      (node (ref "RN1") (pin "2") (pinfunction "2_2") (pintype "passive"))
    )
    (net (code "14") (name "EMAC-TXD0") (class "Default")
      (node (ref "ESP1") (pin "31") (pinfunction "GPIO19_31") (pintype "bidirectional"))
      (node (ref "IC1") (pin "22") (pinfunction "TXD0_22") (pintype "input"))
    )
    (net (code "15") (name "EMAC-TXD1") (class "Default")
      (node (ref "ESP1") (pin "36") (pinfunction "GPIO22_36") (pintype "bidirectional"))
      (node (ref "IC1") (pin "23") (pinfunction "TXD1_23") (pintype "input"))
    )
    (net (code "16") (name "EMAC-TXEN") (class "Default")
      (node (ref "ESP1") (pin "33") (pinfunction "GPIO21_33") (pintype "bidirectional"))
      (node (ref "IC1") (pin "21") (pinfunction "TXEN_21") (pintype "input"))
    )
    (net (code "17") (name "ESP-BUTTON") (class "Default")
      (node (ref "ESP1") (pin "6") (pinfunction "GPIO34_6") (pintype "bidirectional"))
      (node (ref "OPT") (pin "1") (pinfunction "1_1") (pintype "passive"))
      (node (ref "R34") (pin "1") (pinfunction "1_1") (pintype "passive"))
    )
    (net (code "18") (name "ESP-EN") (class "Default")
      (node (ref "C1") (pin "1") (pinfunction "1_1") (pintype "passive"))
      (node (ref "ESP1") (pin "3") (pinfunction "EN_3") (pintype "input"))
      (node (ref "Q6") (pin "3") (pinfunction "C_3") (pintype "passive"))
      (node (ref "R28") (pin "1") (pinfunction "1_1") (pintype "passive"))
      (node (ref "RST") (pin "1") (pinfunction "1_1") (pintype "passive"))
    )
    (net (code "19") (name "ESP-GPIO0") (class "Default")
      (node (ref "ESP1") (pin "25") (pinfunction "GPIO0_25") (pintype "bidirectional"))
      (node (ref "Q5") (pin "3") (pinfunction "C_3") (pintype "passive"))
    )
    (net (code "20") (name "ESP-RXD") (class "Default")
      (node (ref "ESP1") (pin "34") (pinfunction "U0RXD_34") (pintype "bidirectional"))
      (node (ref "R49") (pin "2") (pinfunction "2_2") (pintype "passive"))
    )
    (net (code "21") (name "ESP-SCL") (class "Default")
      (node (ref "ESP1") (pin "27") (pinfunction "GPIO16_27") (pintype "bidirectional"))
      (node (ref "RN4") (pin "2") (pinfunction "2_2") (pintype "passive"))
      (node (ref "UEXT") (pin "5") (pinfunction "5_5") (pintype "passive"))
    )
    (net (code "22") (name "ESP-SD-CLK") (class "Default")
      (node (ref "ESP1") (pin "13") (pinfunction "GPIO14_13") (pintype "bidirectional"))
      (node (ref "R33") (pin "1") (pinfunction "1_1") (pintype "passive"))
      (node (ref "UEXT") (pin "9") (pinfunction "9_9") (pintype "passive"))
    )
    (net (code "23") (name "ESP-SD-CMD") (class "Default")
      (node (ref "ESP1") (pin "23") (pinfunction "GPIO15_23") (pintype "bidirectional"))
      (node (ref "R32") (pin "1") (pinfunction "1_1") (pintype "passive"))
      (node (ref "UEXT") (pin "7") (pinfunction "7_7") (pintype "passive"))
      (node (ref "USD") (pin "3") (pinfunction "CMD_3") (pintype "bidirectional"))
    )
    (net (code "24") (name "ESP-SD-DATA") (class "Default")
      (node (ref "ESP1") (pin "24") (pinfunction "GPIO2_24") (pintype "bidirectional"))
      (node (ref "R31") (pin "1") (pinfunction "1_1") (pintype "passive"))
      (node (ref "RN3") (pin "4") (pinfunction "4_4") (pintype "passive"))
      (node (ref "UEXT") (pin "8") (pinfunction "8_8") (pintype "passive"))
    )
    (net (code "25") (name "ESP-SDA") (class "Default")
      (node (ref "ESP1") (pin "16") (pinfunction "GPIO13_16") (pintype "bidirectional"))
      (node (ref "RN4") (pin "3") (pinfunction "3_3") (pintype "passive"))
      (node (ref "UEXT") (pin "6") (pinfunction "6_6") (pintype "passive"))
    )
    (net (code "26") (name "ESP-SSEL") (class "Default")
      (node (ref "ESP1") (pin "29") (pinfunction "GPIO5_29") (pintype "bidirectional"))
      (node (ref "RN4") (pin "1") (pinfunction "1_1") (pintype "passive"))
      (node (ref "UEXT") (pin "10") (pinfunction "10_10") (pintype "passive"))
    )
    (net (code "27") (name "ESP-TXD") (class "Default")
      (node (ref "ESP1") (pin "35") (pinfunction "U0TXD_35") (pintype "bidirectional"))
      (node (ref "IC6") (pin "9") (pinfunction "RXD_9") (pintype "input"))
    )
    (net (code "28") (name "ETH-LED1") (class "Default")
      (node (ref "IC1") (pin "3") (pinfunction "LED1/REGOFF_3") (pintype "bidirectional"))
      (node (ref "R29") (pin "2") (pinfunction "2_2") (pintype "passive"))
    )
    (net (code "29") (name "ETH-LED2") (class "Default")
      (node (ref "IC1") (pin "2") (pinfunction "LED2/NINTSEL_2") (pintype "bidirectional"))
      (node (ref "R30") (pin "2") (pinfunction "2_2") (pintype "passive"))
    )
    (net (code "30") (name "ETH-PHYAD0") (class "Default")
      (node (ref "IC1") (pin "13") (pinfunction "RXER/RXD4/PHYAD0_13") (pintype "bidirectional"))
      (node (ref "RN2") (pin "3") (pinfunction "3_3") (pintype "passive"))
    )
    (net (code "31") (name "ETH-PHYAD1") (class "Default")
      (node (ref "IC1") (pin "7") (pinfunction "RXCLK/PHYAD1_7") (pintype "bidirectional"))
      (node (ref "RN2") (pin "4") (pinfunction "4_4") (pintype "passive"))
    )
    (net (code "32") (name "ETH-PHYAD2") (class "Default")
      (node (ref "IC1") (pin "8") (pinfunction "RXD3/PHYAD2_8") (pintype "bidirectional"))
      (node (ref "RN1") (pin "4") (pinfunction "4_4") (pintype "passive"))
    )
    (net (code "33") (name "ETH-RMIISEL") (class "Default")
      (node (ref "IC1") (pin "9") (pinfunction "RXD2/RMIISEL_9") (pintype "bidirectional"))
      (node (ref "RN1") (pin "3") (pinfunction "3_3") (pintype "passive"))
    )
    (net (code "34") (name "ETH-VDDA") (class "Default")
      (node (ref "C3") (pin "1") (pinfunction "1_1") (pintype "passive"))
      (node (ref "C6") (pin "1") (pinfunction "1_1") (pintype "passive"))
      (node (ref "C8") (pin "1") (pinfunction "1_1") (pintype "passive"))
      (node (ref "C9") (pin "1") (pinfunction "1_1") (pintype "passive"))
      (node (ref "IC1") (pin "1") (pinfunction "VDD2A_1") (pintype "power_in"))
      (node (ref "IC1") (pin "27") (pinfunction "VDD1A_27") (pintype "power_in"))
      (node (ref "L1") (pin "2") (pinfunction "2_2") (pintype "passive"))
      (node (ref "POE-ETH") (pin "13") (pinfunction "GA_13") (pintype "passive"))
      (node (ref "POE-ETH") (pin "3") (pinfunction "CR_3") (pintype "passive"))
      (node (ref "POE-ETH") (pin "4") (pinfunction "CT_4") (pintype "passive"))
      (node (ref "R15") (pin "2") (pinfunction "2_2") (pintype "passive"))
      (node (ref "R16") (pin "1") (pinfunction "1_1") (pintype "passive"))
      (node (ref "R17") (pin "2") (pinfunction "2_2") (pintype "passive"))
      (node (ref "R18") (pin "1") (pinfunction "1_1") (pintype "passive"))
    )
    (net (code "35") (name "ETH-VDDIO") (class "Default")
      (node (ref "C11") (pin "1") (pinfunction "1_1") (pintype "passive"))
      (node (ref "C5") (pin "1") (pinfunction "1_1") (pintype "passive"))
      (node (ref "IC1") (pin "12") (pinfunction "VDDIO_12") (pintype "power_in"))
      (node (ref "L1") (pin "1") (pinfunction "1_1") (pintype "passive"))
      (node (ref "Q4") (pin "3") (pinfunction "D_3") (pintype "passive"))
      (node (ref "R19") (pin "2") (pinfunction "2_2") (pintype "passive"))
      (node (ref "RN1") (pin "6") (pinfunction "6_6") (pintype "passive"))
      (node (ref "RN1") (pin "7") (pinfunction "7_7") (pintype "passive"))
      (node (ref "RN1") (pin "8") (pinfunction "8_8") (pintype "passive"))
      (node (ref "RN2") (pin "7") (pinfunction "7_7") (pintype "passive"))
      (node (ref "RN2") (pin "8") (pinfunction "8_8") (pintype "passive"))
    )
    (net (code "36") (name "GND") (class "Default")
      (node (ref "C1") (pin "2") (pinfunction "2_2") (pintype "passive"))
      (node (ref "C10") (pin "2") (pinfunction "2_2") (pintype "passive"))
      (node (ref "C11") (pin "2") (pinfunction "2_2") (pintype "passive"))
      (node (ref "C12") (pin "2") (pinfunction "2_2") (pintype "passive"))
      (node (ref "C15") (pin "2") (pinfunction "2_2") (pintype "passive"))
      (node (ref "C16") (pin "2") (pinfunction "2_2") (pintype "passive"))
      (node (ref "C2") (pin "2") (pinfunction "2_2") (pintype "passive"))
      (node (ref "C21") (pin "2") (pinfunction "2_2") (pintype "passive"))
      (node (ref "C23") (pin "2") (pinfunction "2_2") (pintype "passive"))
      (node (ref "C24") (pin "2") (pinfunction "2_2") (pintype "passive"))
      (node (ref "C25") (pin "2") (pinfunction "2_2") (pintype "passive"))
      (node (ref "C26") (pin "2") (pinfunction "2_2") (pintype "passive"))
      (node (ref "C27") (pin "2") (pinfunction "2_2") (pintype "passive"))
      (node (ref "C3") (pin "2") (pinfunction "2_2") (pintype "passive"))
      (node (ref "C5") (pin "2") (pinfunction "2_2") (pintype "passive"))
      (node (ref "C6") (pin "2") (pinfunction "2_2") (pintype "passive"))
      (node (ref "C7") (pin "2") (pinfunction "2_2") (pintype "passive"))
      (node (ref "C8") (pin "2") (pinfunction "2_2") (pintype "passive"))
      (node (ref "C9") (pin "2") (pinfunction "2_2") (pintype "passive"))
      (node (ref "D5") (pin "A") (pinfunction "A_A") (pintype "passive"))
      (node (ref "DC1") (pin "5") (pinfunction "-VOUT_5") (pintype "passive"))
      (node (ref "ESP1") (pin "1") (pinfunction "GND_1") (pintype "power_in"))
      (node (ref "ESP1") (pin "15") (pinfunction "GND_15") (pintype "power_in"))
      (node (ref "ESP1") (pin "38") (pinfunction "GND_38") (pintype "power_in"))
      (node (ref "ESP1") (pin "EP1") (pinfunction "EP_EP1") (pintype "passive"))
      (node (ref "ESP1") (pin "EP2") (pinfunction "EP_EP2") (pintype "passive"))
      (node (ref "ESP1") (pin "EP3") (pinfunction "EP_EP3") (pintype "passive"))
      (node (ref "ESP1") (pin "EP4") (pinfunction "EP_EP4") (pintype "passive"))
      (node (ref "ESP1") (pin "EP5") (pinfunction "EP_EP5") (pintype "passive"))
      (node (ref "ESP1") (pin "EP6") (pinfunction "EP_EP6") (pintype "passive"))
      (node (ref "ESP1") (pin "EP7") (pinfunction "EP_EP7") (pintype "passive"))
      (node (ref "ESP1") (pin "EP8") (pinfunction "EP_EP8") (pintype "passive"))
      (node (ref "ESP1") (pin "EP9") (pinfunction "EP_EP9") (pintype "passive"))
      (node (ref "IC1") (pin "24") (pinfunction "TXD2_24") (pintype "input"))
      (node (ref "IC1") (pin "25") (pinfunction "TXD3_25") (pintype "input"))
      (node (ref "IC1") (pin "EP") (pinfunction "GND_EP") (pintype "power_in"))
      (node (ref "IC4") (pin "2") (pinfunction "GND_2") (pintype "power_in"))
      (node (ref "IC6") (pin "3") (pinfunction "GND_3") (pintype "power_in"))
      (node (ref "OK2") (pin "2") (pinfunction "C_2") (pintype "passive"))
      (node (ref "PGD") (pin "C") (pinfunction "C_C") (pintype "passive"))
      (node (ref "POE-ETH") (pin "12") (pinfunction "YK_12") (pintype "passive"))
      (node (ref "Q3") (pin "2") (pinfunction "E_2") (pintype "passive"))
      (node (ref "R11") (pin "2") (pinfunction "2_2") (pintype "passive"))
      (node (ref "R20") (pin "1") (pinfunction "1_1") (pintype "passive"))
      (node (ref "R35") (pin "2") (pinfunction "2_2") (pintype "passive"))
      (node (ref "R42") (pin "2") (pinfunction "2_2") (pintype "passive"))
      (node (ref "R44") (pin "2") (pinfunction "2_2") (pintype "passive"))
      (node (ref "R47") (pin "2") (pinfunction "2_2") (pintype "passive"))
      (node (ref "R5") (pin "2") (pinfunction "2_2") (pintype "passive"))
      (node (ref "R8") (pin "1") (pinfunction "1_1") (pintype "passive"))
      (node (ref "RN1") (pin "5") (pinfunction "5_5") (pintype "passive"))
      (node (ref "RN2") (pin "5") (pinfunction "5_5") (pintype "passive"))
      (node (ref "RN2") (pin "6") (pinfunction "6_6") (pintype "passive"))
      (node (ref "RST") (pin "3") (pinfunction "3_3") (pintype "passive"))
      (node (ref "RST") (pin "4") (pinfunction "4_4") (pintype "passive"))
      (node (ref "U1") (pin "2") (pinfunction "GND_2") (pintype "power_in"))
      (node (ref "U2") (pin "2") (pinfunction "GND_2") (pintype "power_in"))
      (node (ref "UEXT") (pin "2") (pinfunction "2_2") (pintype "passive"))
      (node (ref "USB") (pin "GND") (pinfunction "GND_GND") (pintype "bidirectional"))
      (node (ref "USB") (pin "MT1") (pinfunction "GND_MT1") (pintype "bidirectional"))
      (node (ref "USB") (pin "MT2") (pinfunction "GND_MT2") (pintype "bidirectional"))
      (node (ref "USB") (pin "MT3") (pinfunction "GND_MT3") (pintype "bidirectional"))
      (node (ref "USB") (pin "MT4") (pinfunction "GND_MT4") (pintype "bidirectional"))
      (node (ref "USB") (pin "MT5") (pinfunction "GND_MT5") (pintype "bidirectional"))
      (node (ref "USB") (pin "MT6") (pinfunction "GND_MT6") (pintype "bidirectional"))
      (node (ref "USD") (pin "6") (pinfunction "GND_6") (pintype "power_in"))
      (node (ref "USD") (pin "S1") (pinfunction "SHIELD_S1") (pintype "passive"))
      (node (ref "USD") (pin "S2") (pinfunction "SHIELD_S2") (pintype "passive"))
      (node (ref "USD") (pin "S3") (pinfunction "SHIELD_S3") (pintype "passive"))
      (node (ref "USD") (pin "S4") (pinfunction "SHIELD_S4") (pintype "passive"))
    )
    (net (code "37") (name "Net-(BSB-Pad1)") (class "Default")
      (node (ref "BSB") (pin "1") (pinfunction "1_1") (pintype "passive"))
      (node (ref "R10") (pin "1") (pinfunction "1_1") (pintype "passive"))
    )
    (net (code "38") (name "Net-(BSBB-1)") (class "Default")
      (node (ref "BSB") (pin "2") (pinfunction "1_2") (pintype "passive"))
      (node (ref "R9") (pin "1") (pinfunction "1_1") (pintype "passive"))
    )
    (net (code "39") (name "Net-(C2-Pad1)") (class "Default")
      (node (ref "C2") (pin "1") (pinfunction "1_1") (pintype "passive"))
      (node (ref "POE-ETH") (pin "SH1") (pinfunction "SLD_SH1") (pintype "passive"))
      (node (ref "POE-ETH") (pin "SH2") (pinfunction "SLD_SH2") (pintype "passive"))
    )
    (net (code "40") (name "Net-(C17-Pad1)") (class "Default")
      (node (ref "C17") (pin "1") (pinfunction "1_1") (pintype "passive"))
      (node (ref "R39") (pin "2") (pinfunction "2_2") (pintype "passive"))
    )
    (net (code "41") (name "Net-(D2-PadC)") (class "Default")
      (node (ref "D2") (pin "C") (pinfunction "C_C") (pintype "passive"))
      (node (ref "D3") (pin "1") (pinfunction "1_1") (pintype "passive"))
      (node (ref "R9") (pin "2") (pinfunction "2_2") (pintype "passive"))
    )
    (net (code "42") (name "Net-(IC1-NRST)") (class "Default")
      (node (ref "C12") (pin "1") (pinfunction "1_1") (pintype "passive"))
      (node (ref "IC1") (pin "19") (pinfunction "NRST_19") (pintype "input"))
      (node (ref "R19") (pin "1") (pinfunction "1_1") (pintype "passive"))
    )
    (net (code "43") (name "Net-(IC1-RBIAS)") (class "Default")
      (node (ref "IC1") (pin "32") (pinfunction "RBIAS_32") (pintype "passive"))
      (node (ref "R20") (pin "2") (pinfunction "2_2") (pintype "passive"))
    )
    (net (code "44") (name "Net-(IC1-RXN)") (class "Default")
      (node (ref "IC1") (pin "30") (pinfunction "RXN_30") (pintype "bidirectional"))
      (node (ref "POE-ETH") (pin "2") (pinfunction "RD-_2") (pintype "passive"))
      (node (ref "R17") (pin "1") (pinfunction "1_1") (pintype "passive"))
      (node (ref "U1") (pin "3") (pinfunction "IO2_3") (pintype "passive"))
    )
    (net (code "45") (name "Net-(IC1-RXP)") (class "Default")
      (node (ref "IC1") (pin "31") (pinfunction "RXP_31") (pintype "bidirectional"))
      (node (ref "POE-ETH") (pin "1") (pinfunction "RD+_1") (pintype "passive"))
      (node (ref "R18") (pin "2") (pinfunction "2_2") (pintype "passive"))
      (node (ref "U1") (pin "4") (pinfunction "IO3_4") (pintype "passive"))
    )
    (net (code "46") (name "Net-(IC1-TXN)") (class "Default")
      (node (ref "IC1") (pin "28") (pinfunction "TXN_28") (pintype "bidirectional"))
      (node (ref "POE-ETH") (pin "6") (pinfunction "TD-_6") (pintype "passive"))
      (node (ref "R15") (pin "1") (pinfunction "1_1") (pintype "passive"))
      (node (ref "U1") (pin "5") (pinfunction "IO4_5") (pintype "passive"))
    )
    (net (code "47") (name "Net-(IC1-TXP)") (class "Default")
      (node (ref "IC1") (pin "29") (pinfunction "TXP_29") (pintype "bidirectional"))
      (node (ref "POE-ETH") (pin "5") (pinfunction "TD+_5") (pintype "passive"))
      (node (ref "R16") (pin "2") (pinfunction "2_2") (pintype "passive"))
      (node (ref "U1") (pin "1") (pinfunction "IO1_1") (pintype "passive"))
    )
    (net (code "48") (name "Net-(IC1-VDDCR)") (class "Default")
      (node (ref "C10") (pin "1") (pinfunction "1_1") (pintype "passive"))
      (node (ref "C7") (pin "1") (pinfunction "1_1") (pintype "passive"))
      (node (ref "IC1") (pin "6") (pinfunction "VDDCR_6") (pintype "power_in"))
    )
    (net (code "49") (name "Net-(IC2-CLASS)") (class "Default")
      (node (ref "IC2") (pin "2") (pinfunction "CLASS_2") (pintype "input"))
      (node (ref "R27") (pin "1") (pinfunction "1_1") (pintype "passive"))
    )
    (net (code "50") (name "Net-(IC2-DET)") (class "Default")
      (node (ref "IC2") (pin "3") (pinfunction "DET_3") (pintype "input"))
      (node (ref "R25") (pin "2") (pinfunction "2_2") (pintype "passive"))
    )
    (net (code "51") (name "Net-(IC2-ILIM)") (class "Default")
      (node (ref "IC2") (pin "1") (pinfunction "ILIM_1") (pintype "input"))
      (node (ref "R26") (pin "1") (pinfunction "1_1") (pintype "passive"))
    )
    (net (code "52") (name "Net-(IC2-UVLO)") (class "Default")
      (node (ref "IC2") (pin "7") (pinfunction "UVLO_7") (pintype "input"))
      (node (ref "R23") (pin "1") (pinfunction "1_1") (pintype "passive"))
      (node (ref "R24") (pin "2") (pinfunction "2_2") (pintype "passive"))
    )
    (net (code "53") (name "Net-(IC3-BS)") (class "Default")
      (node (ref "IC3") (pin "8") (pinfunction "BS_8") (pintype "power_in"))
      (node (ref "R39") (pin "1") (pinfunction "1_1") (pintype "passive"))
    )
    (net (code "54") (name "Net-(IC3-FB)") (class "Default")
      (node (ref "C19") (pin "2") (pinfunction "2_2") (pintype "passive"))
      (node (ref "IC3") (pin "5") (pinfunction "FB_5") (pintype "input"))
      (node (ref "R36") (pin "1") (pinfunction "1_1") (pintype "passive"))
      (node (ref "R37") (pin "1") (pinfunction "1_1") (pintype "passive"))
    )
    (net (code "55") (name "Net-(IC3-ILIM-Pad2)") (class "Default")
      (node (ref "IC3") (pin "2") (pinfunction "ILIM_2") (pintype "power_in"))
      (node (ref "IC3") (pin "EP") (pinfunction "ILIM_EP") (pintype "power_in"))
      (node (ref "R21") (pin "2") (pinfunction "2_2") (pintype "passive"))
    )
    (net (code "56") (name "Net-(IC3-SW)") (class "Default")
      (node (ref "C17") (pin "2") (pinfunction "2_2") (pintype "passive"))
      (node (ref "D1") (pin "C") (pinfunction "C_C") (pintype "passive"))
      (node (ref "IC3") (pin "1") (pinfunction "SW_1") (pintype "output"))
      (node (ref "L3") (pin "1") (pinfunction "1_1") (pintype "passive"))
    )
    (net (code "57") (name "Net-(IC4-FB)") (class "Default")
      (node (ref "IC4") (pin "5") (pinfunction "FB_5") (pintype "input"))
      (node (ref "R40") (pin "1") (pinfunction "1_1") (pintype "passive"))
      (node (ref "R41") (pin "2") (pinfunction "2_2") (pintype "passive"))
    )
    (net (code "58") (name "Net-(IC4-LX)") (class "Default")
      (node (ref "IC4") (pin "3") (pinfunction "LX_3") (pintype "output"))
      (node (ref "L4") (pin "1") (pinfunction "1_1") (pintype "passive"))
    )
    (net (code "59") (name "Net-(IC6-TNOW{slash}~{DTR})") (class "Default")
      (node (ref "IC6") (pin "6") (pinfunction "TNOW/~{DTR}_6") (pintype "bidirectional"))
      (node (ref "Q5") (pin "2") (pinfunction "E_2") (pintype "passive"))
      (node (ref "R46") (pin "2") (pinfunction "2_2") (pintype "passive"))
      (node (ref "R50") (pin "1") (pinfunction "1_1") (pintype "passive"))
    )
    (net (code "60") (name "Net-(IC6-TXD)") (class "Default")
      (node (ref "IC6") (pin "8") (pinfunction "TXD_8") (pintype "output"))
      (node (ref "R49") (pin "1") (pinfunction "1_1") (pintype "passive"))
    )
    (net (code "61") (name "Net-(IC6-~{CTS})") (class "Default")
      (node (ref "IC6") (pin "5") (pinfunction "~{CTS}_5") (pintype "input"))
      (node (ref "R50") (pin "2") (pinfunction "2_2") (pintype "passive"))
    )
    (net (code "62") (name "Net-(IC6-~{RTS})") (class "Default")
      (node (ref "IC6") (pin "4") (pinfunction "~{RTS}_4") (pintype "output"))
      (node (ref "Q6") (pin "2") (pinfunction "E_2") (pintype "passive"))
      (node (ref "R45") (pin "2") (pinfunction "2_2") (pintype "passive"))
    )
    (net (code "63") (name "Net-(OK1-A)") (class "Default")
      (node (ref "OK1") (pin "1") (pinfunction "A_1") (pintype "passive"))
      (node (ref "R2") (pin "2") (pinfunction "2_2") (pintype "passive"))
    )
    (net (code "64") (name "Net-(OK1-BAS)") (class "Default")
      (node (ref "OK1") (pin "6") (pinfunction "BAS_6") (pintype "passive"))
      (node (ref "R4") (pin "2") (pinfunction "2_2") (pintype "passive"))
    )
    (net (code "65") (name "Net-(OK1-C)") (class "Default")
      (node (ref "ACT") (pin "A") (pinfunction "A_A") (pintype "passive"))
      (node (ref "OK1") (pin "2") (pinfunction "C_2") (pintype "passive"))
    )
    (net (code "66") (name "Net-(OK2-A)") (class "Default")
      (node (ref "OK2") (pin "1") (pinfunction "A_1") (pintype "passive"))
      (node (ref "R3") (pin "2") (pinfunction "2_2") (pintype "passive"))
    )
    (net (code "67") (name "Net-(OK2-BAS)") (class "Default")
      (node (ref "OK2") (pin "6") (pinfunction "BAS_6") (pintype "passive"))
      (node (ref "R1") (pin "2") (pinfunction "2_2") (pintype "passive"))
    )
    (net (code "68") (name "Net-(OK2-EMI)") (class "Default")
      (node (ref "OK2") (pin "4") (pinfunction "EMI_4") (pintype "passive"))
      (node (ref "Q1") (pin "1") (pinfunction "B_1") (pintype "passive"))
      (node (ref "R1") (pin "1") (pinfunction "1_1") (pintype "passive"))
      (node (ref "R7") (pin "2") (pinfunction "2_2") (pintype "passive"))
    )
    (net (code "69") (name "Net-(OPT-Pad2)") (class "Default")
      (node (ref "OPT") (pin "2") (pinfunction "2_2") (pintype "passive"))
      (node (ref "R35") (pin "1") (pinfunction "1_1") (pintype "passive"))
    )
    (net (code "70") (name "Net-(PGD-PadA)") (class "Default")
      (node (ref "PGD") (pin "A") (pinfunction "A_A") (pintype "passive"))
      (node (ref "R48") (pin "1") (pinfunction "1_1") (pintype "passive"))
    )
    (net (code "71") (name "Net-(POE-ETH-GK)") (class "Default")
      (node (ref "POE-ETH") (pin "14") (pinfunction "GK_14") (pintype "passive"))
      (node (ref "R30") (pin "1") (pinfunction "1_1") (pintype "passive"))
    )
    (net (code "72") (name "Net-(POE-ETH-YA)") (class "Default")
      (node (ref "POE-ETH") (pin "11") (pinfunction "YA_11") (pintype "passive"))
      (node (ref "R29") (pin "1") (pinfunction "1_1") (pintype "passive"))
    )
    (net (code "73") (name "Net-(Q2-PadB)") (class "Default")
      (node (ref "Q2") (pin "B") (pinfunction "B_B") (pintype "passive"))
      (node (ref "R6") (pin "1") (pinfunction "1_1") (pintype "passive"))
    )
    (net (code "74") (name "Net-(Q2-PadC)") (class "Default")
      (node (ref "Q2") (pin "C") (pinfunction "C_C") (pintype "passive"))
      (node (ref "R3") (pin "1") (pinfunction "1_1") (pintype "passive"))
    )
    (net (code "75") (name "Net-(Q3-B)") (class "Default")
      (node (ref "Q3") (pin "1") (pinfunction "B_1") (pintype "passive"))
      (node (ref "R11") (pin "1") (pinfunction "1_1") (pintype "passive"))
      (node (ref "R14") (pin "2") (pinfunction "2_2") (pintype "passive"))
    )
    (net (code "76") (name "Net-(Q3-C)") (class "Default")
      (node (ref "Q3") (pin "3") (pinfunction "C_3") (pintype "passive"))
      (node (ref "R12") (pin "1") (pinfunction "1_1") (pintype "passive"))
    )
    (net (code "77") (name "Net-(Q4-G)") (class "Default")
      (node (ref "C4") (pin "2") (pinfunction "2_2") (pintype "passive"))
      (node (ref "Q4") (pin "1") (pinfunction "G_1") (pintype "passive"))
      (node (ref "R12") (pin "2") (pinfunction "2_2") (pintype "passive"))
      (node (ref "R13") (pin "1") (pinfunction "1_1") (pintype "passive"))
    )
    (net (code "78") (name "Net-(Q5-B)") (class "Default")
      (node (ref "Q5") (pin "1") (pinfunction "B_1") (pintype "passive"))
      (node (ref "R45") (pin "1") (pinfunction "1_1") (pintype "passive"))
    )
    (net (code "79") (name "Net-(Q6-B)") (class "Default")
      (node (ref "Q6") (pin "1") (pinfunction "B_1") (pintype "passive"))
      (node (ref "R46") (pin "1") (pinfunction "1_1") (pintype "passive"))
    )
    (net (code "80") (name "Net-(R36-Pad2)") (class "Default")
      (node (ref "R36") (pin "2") (pinfunction "2_2") (pintype "passive"))
      (node (ref "R38") (pin "2") (pinfunction "2_2") (pintype "passive"))
    )
    (net (code "81") (name "Net-(R41-Pad1)") (class "Default")
      (node (ref "R41") (pin "1") (pinfunction "1_1") (pintype "passive"))
      (node (ref "R42") (pin "1") (pinfunction "1_1") (pintype "passive"))
    )
    (net (code "82") (name "Net-(USD-CS{slash}DAT3)") (class "Default")
      (node (ref "RN3") (pin "2") (pinfunction "2_2") (pintype "passive"))
      (node (ref "USD") (pin "2") (pinfunction "CS/DAT3_2") (pintype "bidirectional"))
    )
    (net (code "83") (name "Net-(USD-DAT0)") (class "Default")
      (node (ref "R31") (pin "2") (pinfunction "2_2") (pintype "passive"))
      (node (ref "USD") (pin "7") (pinfunction "DAT0_7") (pintype "bidirectional"))
    )
    (net (code "84") (name "Net-(USD-DAT1)") (class "Default")
      (node (ref "RN3") (pin "3") (pinfunction "3_3") (pintype "passive"))
      (node (ref "USD") (pin "8") (pinfunction "DAT1_8") (pintype "bidirectional"))
    )
    (net (code "85") (name "Net-(USD-DAT2)") (class "Default")
      (node (ref "RN3") (pin "1") (pinfunction "1_1") (pintype "passive"))
      (node (ref "USD") (pin "1") (pinfunction "DAT2_1") (pintype "bidirectional"))
    )
    (net (code "86") (name "Net-(USD-SCLK)") (class "Default")
      (node (ref "R33") (pin "2") (pinfunction "2_2") (pintype "passive"))
      (node (ref "USD") (pin "5") (pinfunction "SCLK_5") (pintype "bidirectional"))
    )
    (net (code "87") (name "PHY-PWR") (class "Default")
      (node (ref "ESP1") (pin "14") (pinfunction "GPIO12_14") (pintype "bidirectional"))
      (node (ref "R14") (pin "1") (pinfunction "1_1") (pintype "passive"))
    )
    (net (code "88") (name "POE-5V0") (class "Default")
      (node (ref "C18") (pin "+") (pinfunction "+_+") (pintype "passive"))
      (node (ref "C19") (pin "1") (pinfunction "1_1") (pintype "passive"))
      (node (ref "C20") (pin "1") (pinfunction "1_1") (pintype "passive"))
      (node (ref "C22") (pin "1") (pinfunction "1_1") (pintype "passive"))
      (node (ref "DC1") (pin "1") (pinfunction "+VIN_1") (pintype "passive"))
      (node (ref "L3") (pin "2") (pinfunction "2_2") (pintype "passive"))
      (node (ref "R38") (pin "1") (pinfunction "1_1") (pintype "passive"))
    )
    (net (code "89") (name "POE-GND") (class "Default")
      (node (ref "C14") (pin "-") (pinfunction "-_-") (pintype "passive"))
      (node (ref "C18") (pin "-") (pinfunction "-_-") (pintype "passive"))
      (node (ref "C21") (pin "1") (pinfunction "1_1") (pintype "passive"))
      (node (ref "C22") (pin "2") (pinfunction "2_2") (pintype "passive"))
      (node (ref "D1") (pin "A") (pinfunction "A_A") (pintype "passive"))
      (node (ref "DC1") (pin "2") (pinfunction "-VIN_2") (pintype "passive"))
      (node (ref "IC2") (pin "5") (pinfunction "RTN_5") (pintype "power_in"))
      (node (ref "IC3") (pin "4") (pinfunction "GND_4") (pintype "power_in"))
      (node (ref "R22") (pin "2") (pinfunction "2_2") (pintype "passive"))
      (node (ref "R37") (pin "2") (pinfunction "2_2") (pintype "passive"))
    )
    (net (code "90") (name "POE-PG") (class "Default")
      (node (ref "IC2") (pin "6") (pinfunction "PG_6") (pintype "output"))
      (node (ref "IC3") (pin "6") (pinfunction "EN_6") (pintype "input"))
    )
    (net (code "91") (name "POE-V+") (class "Default")
      (node (ref "C13") (pin "1") (pinfunction "1_1") (pintype "passive"))
      (node (ref "C14") (pin "+") (pinfunction "+_+") (pintype "passive"))
      (node (ref "D4") (pin "C") (pinfunction "C_C") (pintype "passive"))
      (node (ref "IC2") (pin "8") (pinfunction "VDD_8") (pintype "power_in"))
      (node (ref "IC3") (pin "3") (pinfunction "VIN_3") (pintype "power_in"))
      (node (ref "POE-ETH") (pin "9") (pinfunction "V+_9") (pintype "output"))
      (node (ref "R21") (pin "1") (pinfunction "1_1") (pintype "passive"))
      (node (ref "R22") (pin "1") (pinfunction "1_1") (pintype "passive"))
      (node (ref "R24") (pin "1") (pinfunction "1_1") (pintype "passive"))
      (node (ref "R25") (pin "1") (pinfunction "1_1") (pintype "passive"))
    )
    (net (code "92") (name "POE-V-") (class "Default")
      (node (ref "C13") (pin "2") (pinfunction "2_2") (pintype "passive"))
      (node (ref "D4") (pin "A") (pinfunction "A_A") (pintype "passive"))
      (node (ref "IC2") (pin "4") (pinfunction "VSS_4") (pintype "power_in"))
      (node (ref "IC2") (pin "EP") (pinfunction "VSS_EP") (pintype "power_in"))
      (node (ref "POE-ETH") (pin "10") (pinfunction "V-_10") (pintype "output"))
      (node (ref "R23") (pin "2") (pinfunction "2_2") (pintype "passive"))
      (node (ref "R26") (pin "2") (pinfunction "2_2") (pintype "passive"))
      (node (ref "R27") (pin "2") (pinfunction "2_2") (pintype "passive"))
    )
    (net (code "93") (name "PWR-SNS") (class "Default")
      (node (ref "C27") (pin "1") (pinfunction "1_1") (pintype "passive"))
      (node (ref "ESP1") (pin "5") (pinfunction "SENSOR_VN_5") (pintype "bidirectional"))
      (node (ref "R43") (pin "2") (pinfunction "2_2") (pintype "passive"))
      (node (ref "R44") (pin "1") (pinfunction "1_1") (pintype "passive"))
    )
    (net (code "94") (name "SD-VCC") (class "Default")
      (node (ref "C15") (pin "1") (pinfunction "1_1") (pintype "passive"))
      (node (ref "C16") (pin "1") (pinfunction "1_1") (pintype "passive"))
      (node (ref "L2") (pin "2") (pinfunction "2_2") (pintype "passive"))
      (node (ref "USD") (pin "4") (pinfunction "VCC_4") (pintype "power_in"))
    )
    (net (code "95") (name "UEXT-RX") (class "Default")
      (node (ref "ESP1") (pin "8") (pinfunction "GPIO32_8") (pintype "bidirectional"))
      (node (ref "RN4") (pin "4") (pinfunction "4_4") (pintype "passive"))
      (node (ref "UEXT") (pin "4") (pinfunction "4_4") (pintype "passive"))
    )
    (net (code "96") (name "UEXT-TX") (class "Default")
      (node (ref "ESP1") (pin "9") (pinfunction "GPIO33_9") (pintype "bidirectional"))
      (node (ref "UEXT") (pin "3") (pinfunction "3_3") (pintype "passive"))
    )
    (net (code "97") (name "USB-D_N") (class "Default")
      (node (ref "IC6") (pin "2") (pinfunction "D-_2") (pintype "bidirectional"))
      (node (ref "U2") (pin "1") (pinfunction "IO1_1") (pintype "passive"))
      (node (ref "USB") (pin "D-") (pinfunction "D-_D-") (pintype "bidirectional"))
    )
    (net (code "98") (name "USB-D_P") (class "Default")
      (node (ref "IC6") (pin "1") (pinfunction "D+_1") (pintype "bidirectional"))
      (node (ref "U2") (pin "5") (pinfunction "IO4_5") (pintype "passive"))
      (node (ref "USB") (pin "D+") (pinfunction "D+_D+") (pintype "bidirectional"))
    )
    (net (code "99") (name "USB-VBUS") (class "Default")
      (node (ref "Q7") (pin "3") (pinfunction "D_3") (pintype "passive"))
      (node (ref "USB") (pin "VBUS") (pinfunction "VCC_VBUS") (pintype "bidirectional"))
    )
    (net (code "100") (name "unconnected-(ESP1-GPIO35-Pad7)") (class "Default")
      (node (ref "ESP1") (pin "7") (pinfunction "GPIO35_7") (pintype "bidirectional"))
    )
    (net (code "101") (name "unconnected-(IC1-CRS-Pad14)") (class "Default")
      (node (ref "IC1") (pin "14") (pinfunction "CRS_14") (pintype "bidirectional"))
    )
    (net (code "102") (name "unconnected-(IC1-RXDV-Pad26)") (class "Default")
      (node (ref "IC1") (pin "26") (pinfunction "RXDV_26") (pintype "bidirectional"))
    )
    (net (code "103") (name "unconnected-(IC1-TXCLK-Pad20)") (class "Default")
      (node (ref "IC1") (pin "20") (pinfunction "TXCLK_20") (pintype "bidirectional"))
    )
    (net (code "104") (name "unconnected-(IC1-TXER{slash}TXD4-Pad18)") (class "Default")
      (node (ref "IC1") (pin "18") (pinfunction "TXER/TXD4_18") (pintype "bidirectional"))
    )
    (net (code "105") (name "unconnected-(IC1-XTAL2-Pad4)") (class "Default")
      (node (ref "IC1") (pin "4") (pinfunction "XTAL2_4") (pintype "output"))
    )
    (net (code "106") (name "unconnected-(IC3-POK-Pad7)") (class "Default")
      (node (ref "IC3") (pin "7") (pinfunction "POK_7") (pintype "output"))
    )
    (net (code "107") (name "unconnected-(RST-Pad2)") (class "Default")
      (node (ref "RST") (pin "2") (pinfunction "2_2") (pintype "passive"))
    )
    (net (code "108") (name "unconnected-(U2-IO3-Pad4)") (class "Default")
      (node (ref "U2") (pin "4") (pinfunction "IO3_4") (pintype "passive"))
    )
    (net (code "109") (name "unconnected-(USB-PadID)") (class "Default")
      (node (ref "USB") (pin "ID") (pinfunction "ID_ID") (pintype "bidirectional"))
    )
    (net (code "110") (name "unconnected-(USD-CDET-Pad9)") (class "Default")
      (node (ref "USD") (pin "9") (pinfunction "CDET_9") (pintype "passive"))
    )
  )
)
